# PSPS_AVNC_SRD_fullBoard-2020-09-23.net
KiCad netlist of a schematic drawn in EAGLE
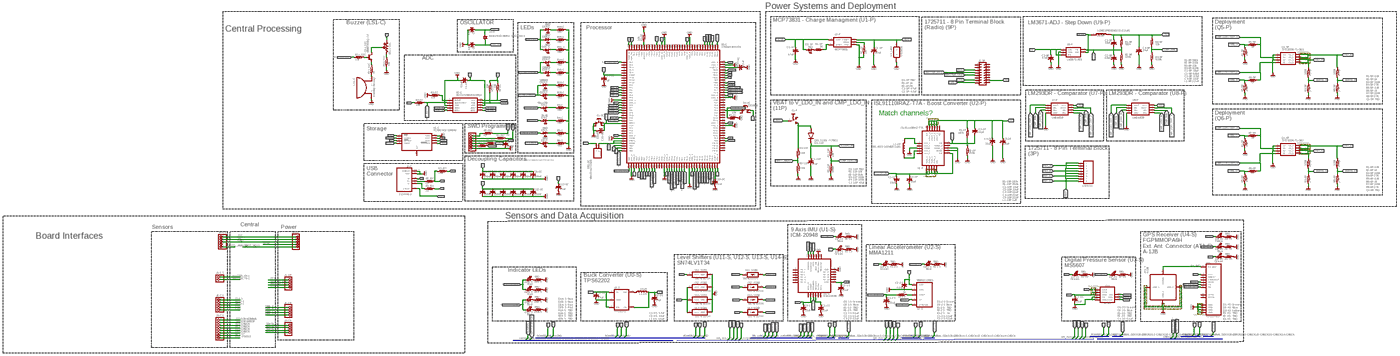
[diagram p0: schematic, sheet 1, overview]
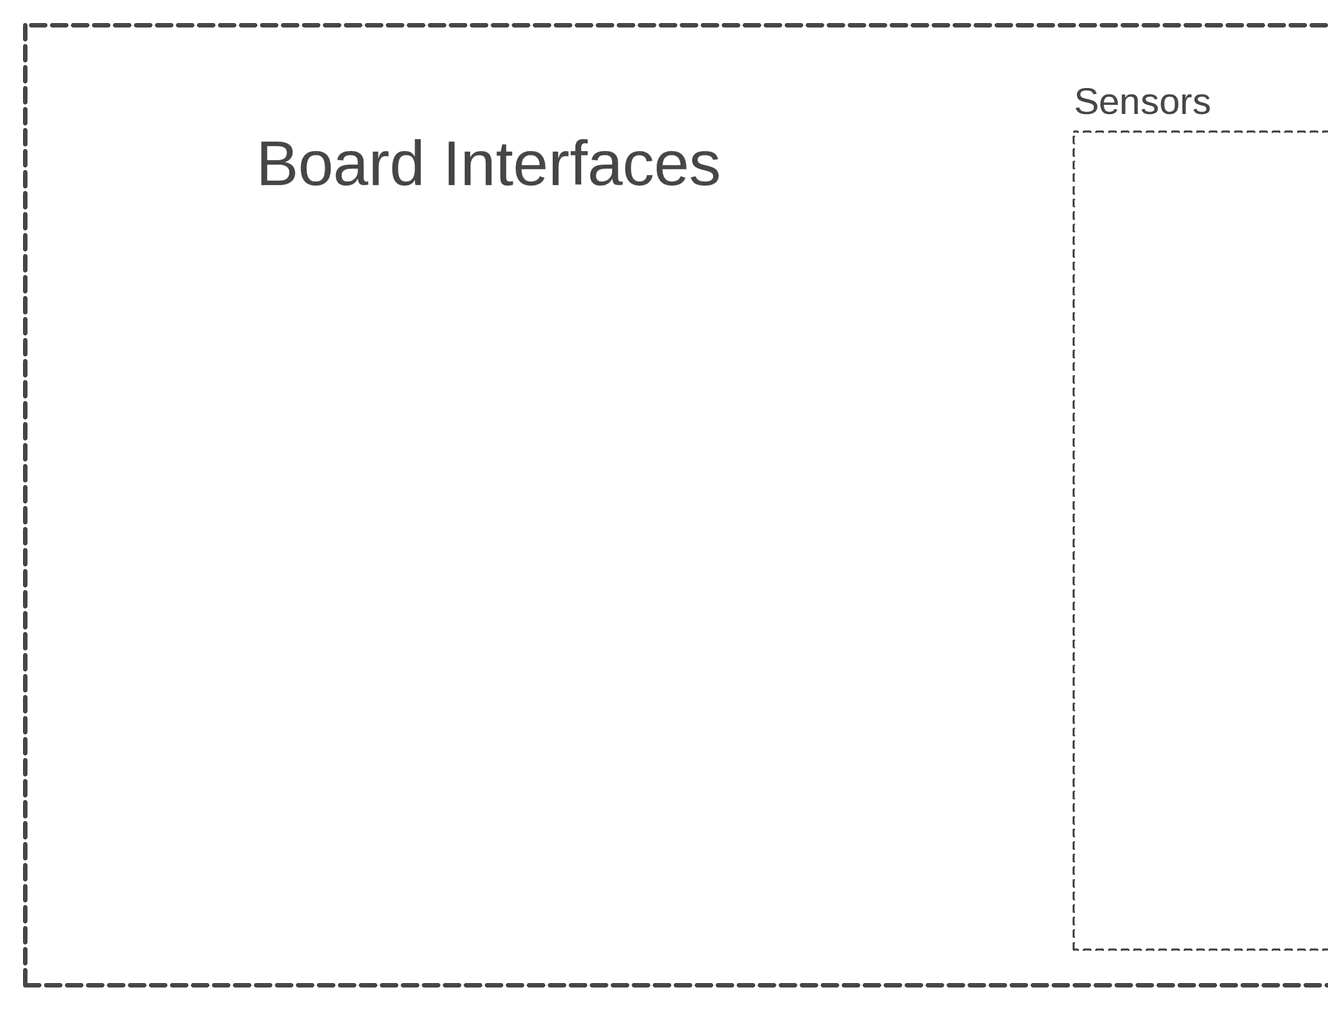
[diagram p1: schematic, sheet 1, part 1 of 4]
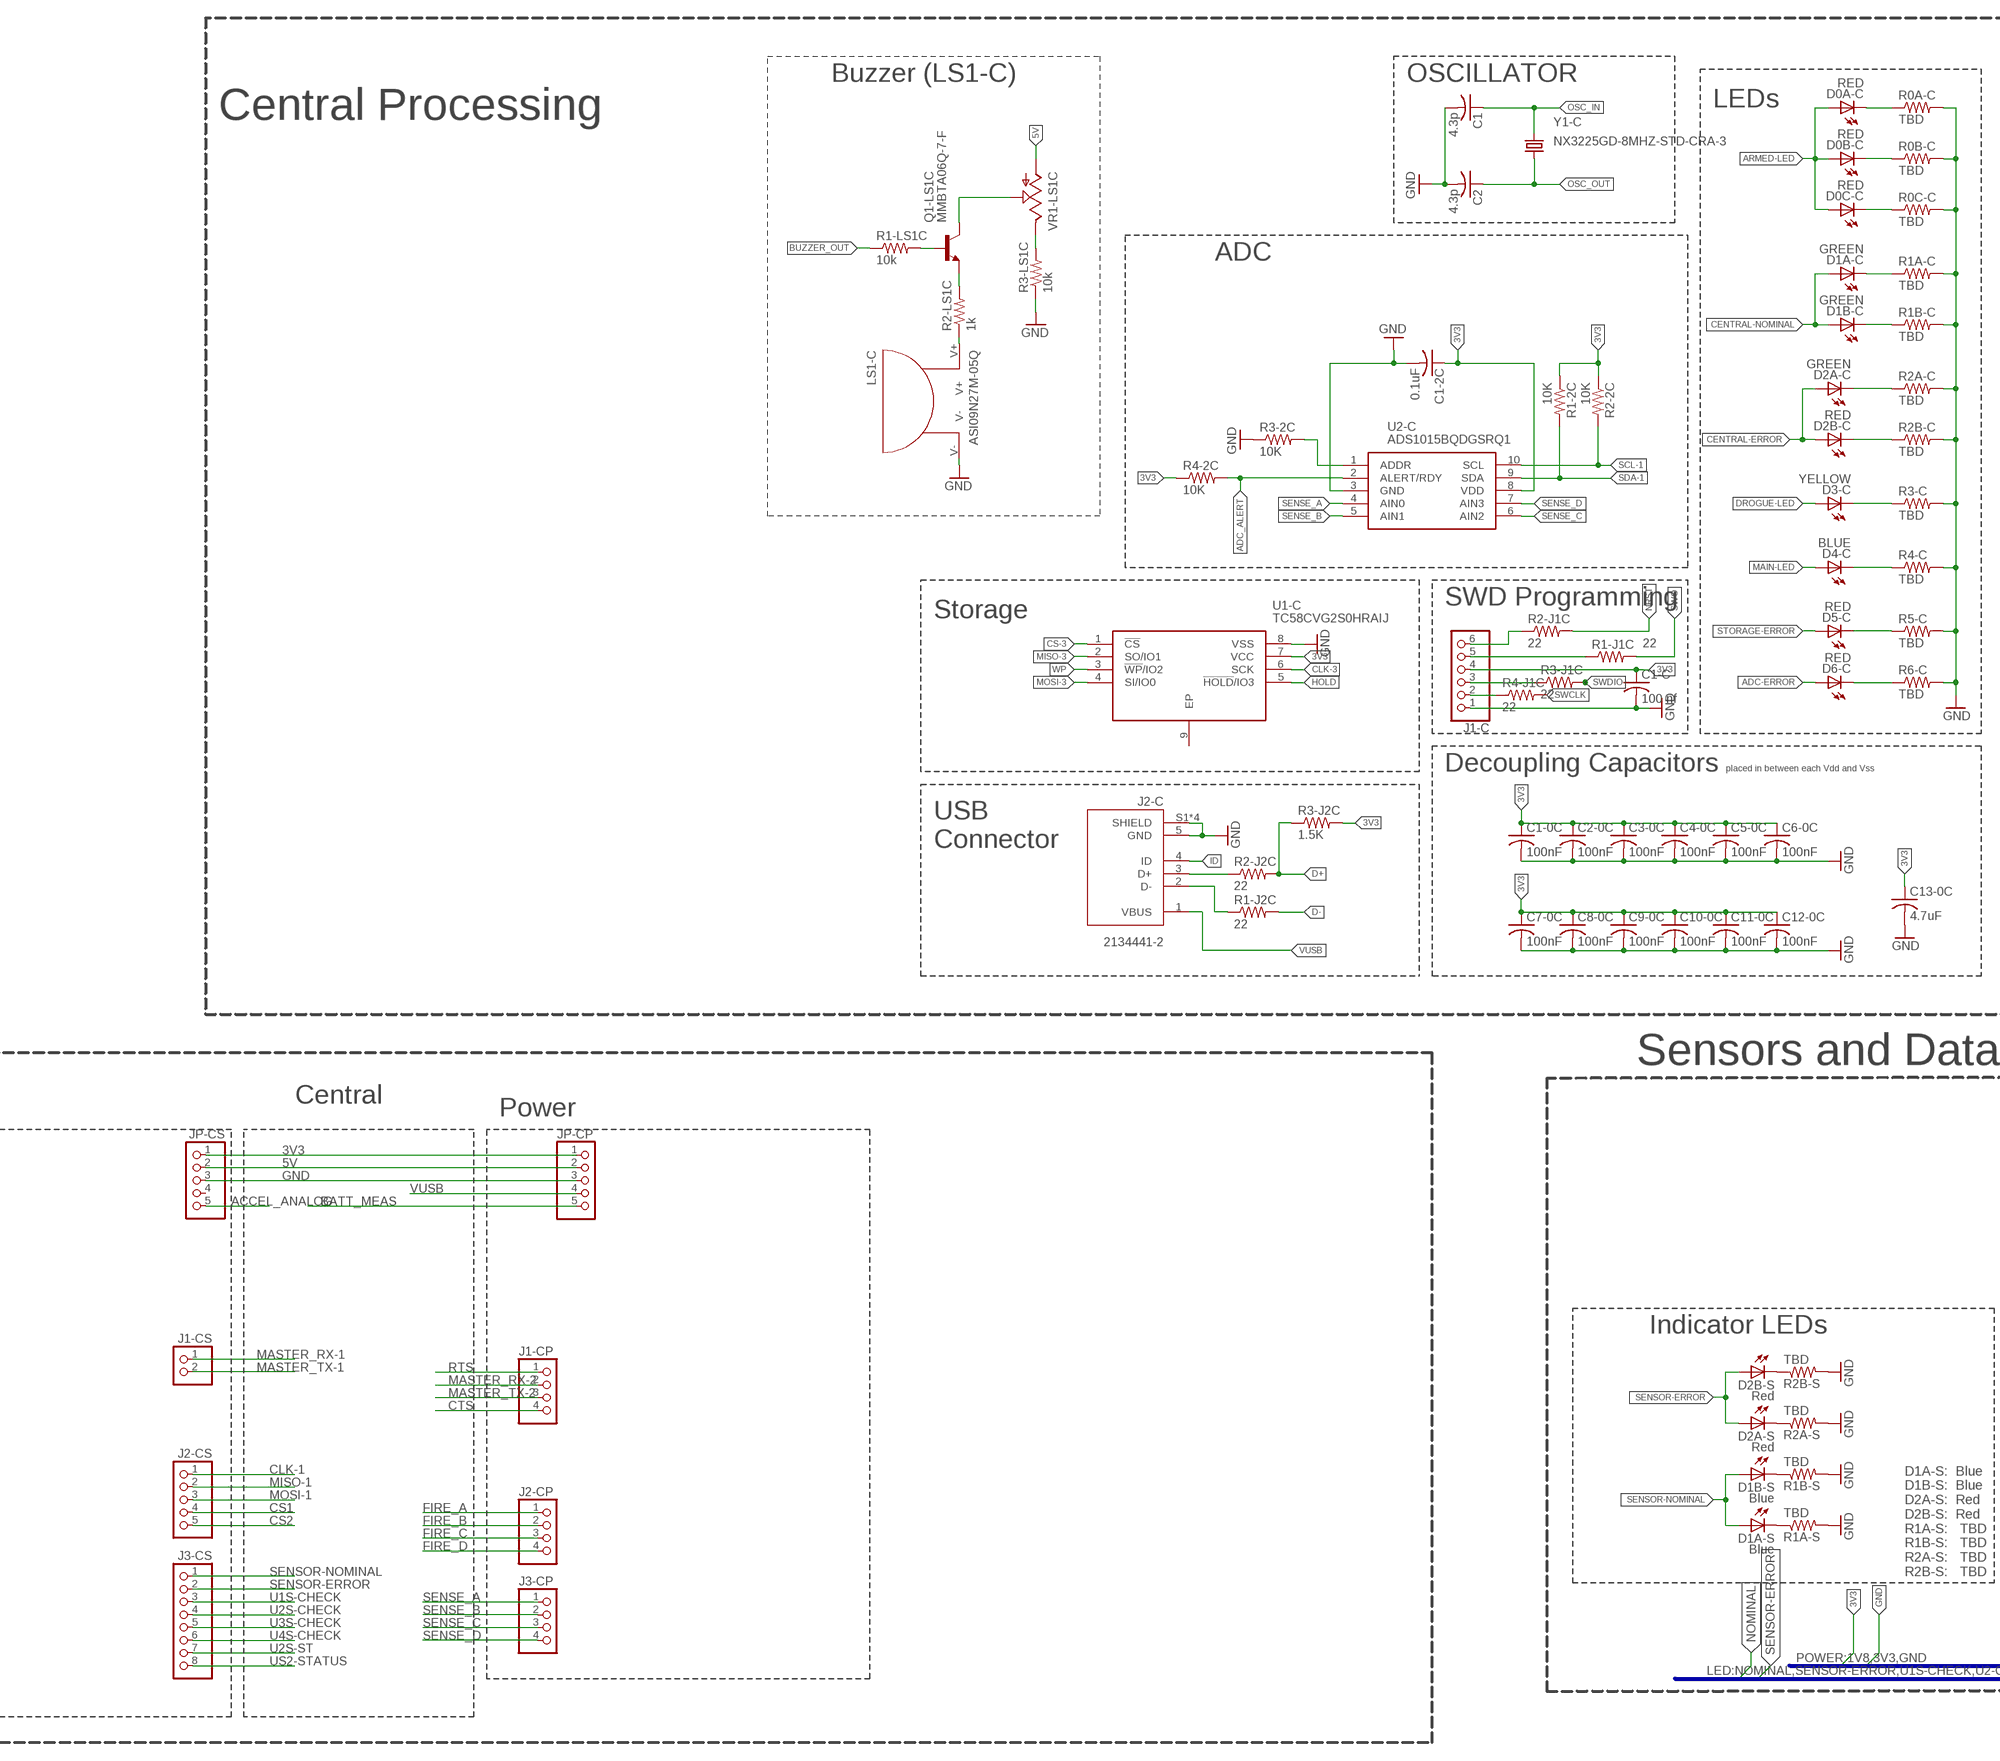
[diagram p2: schematic, sheet 1, part 2 of 4]
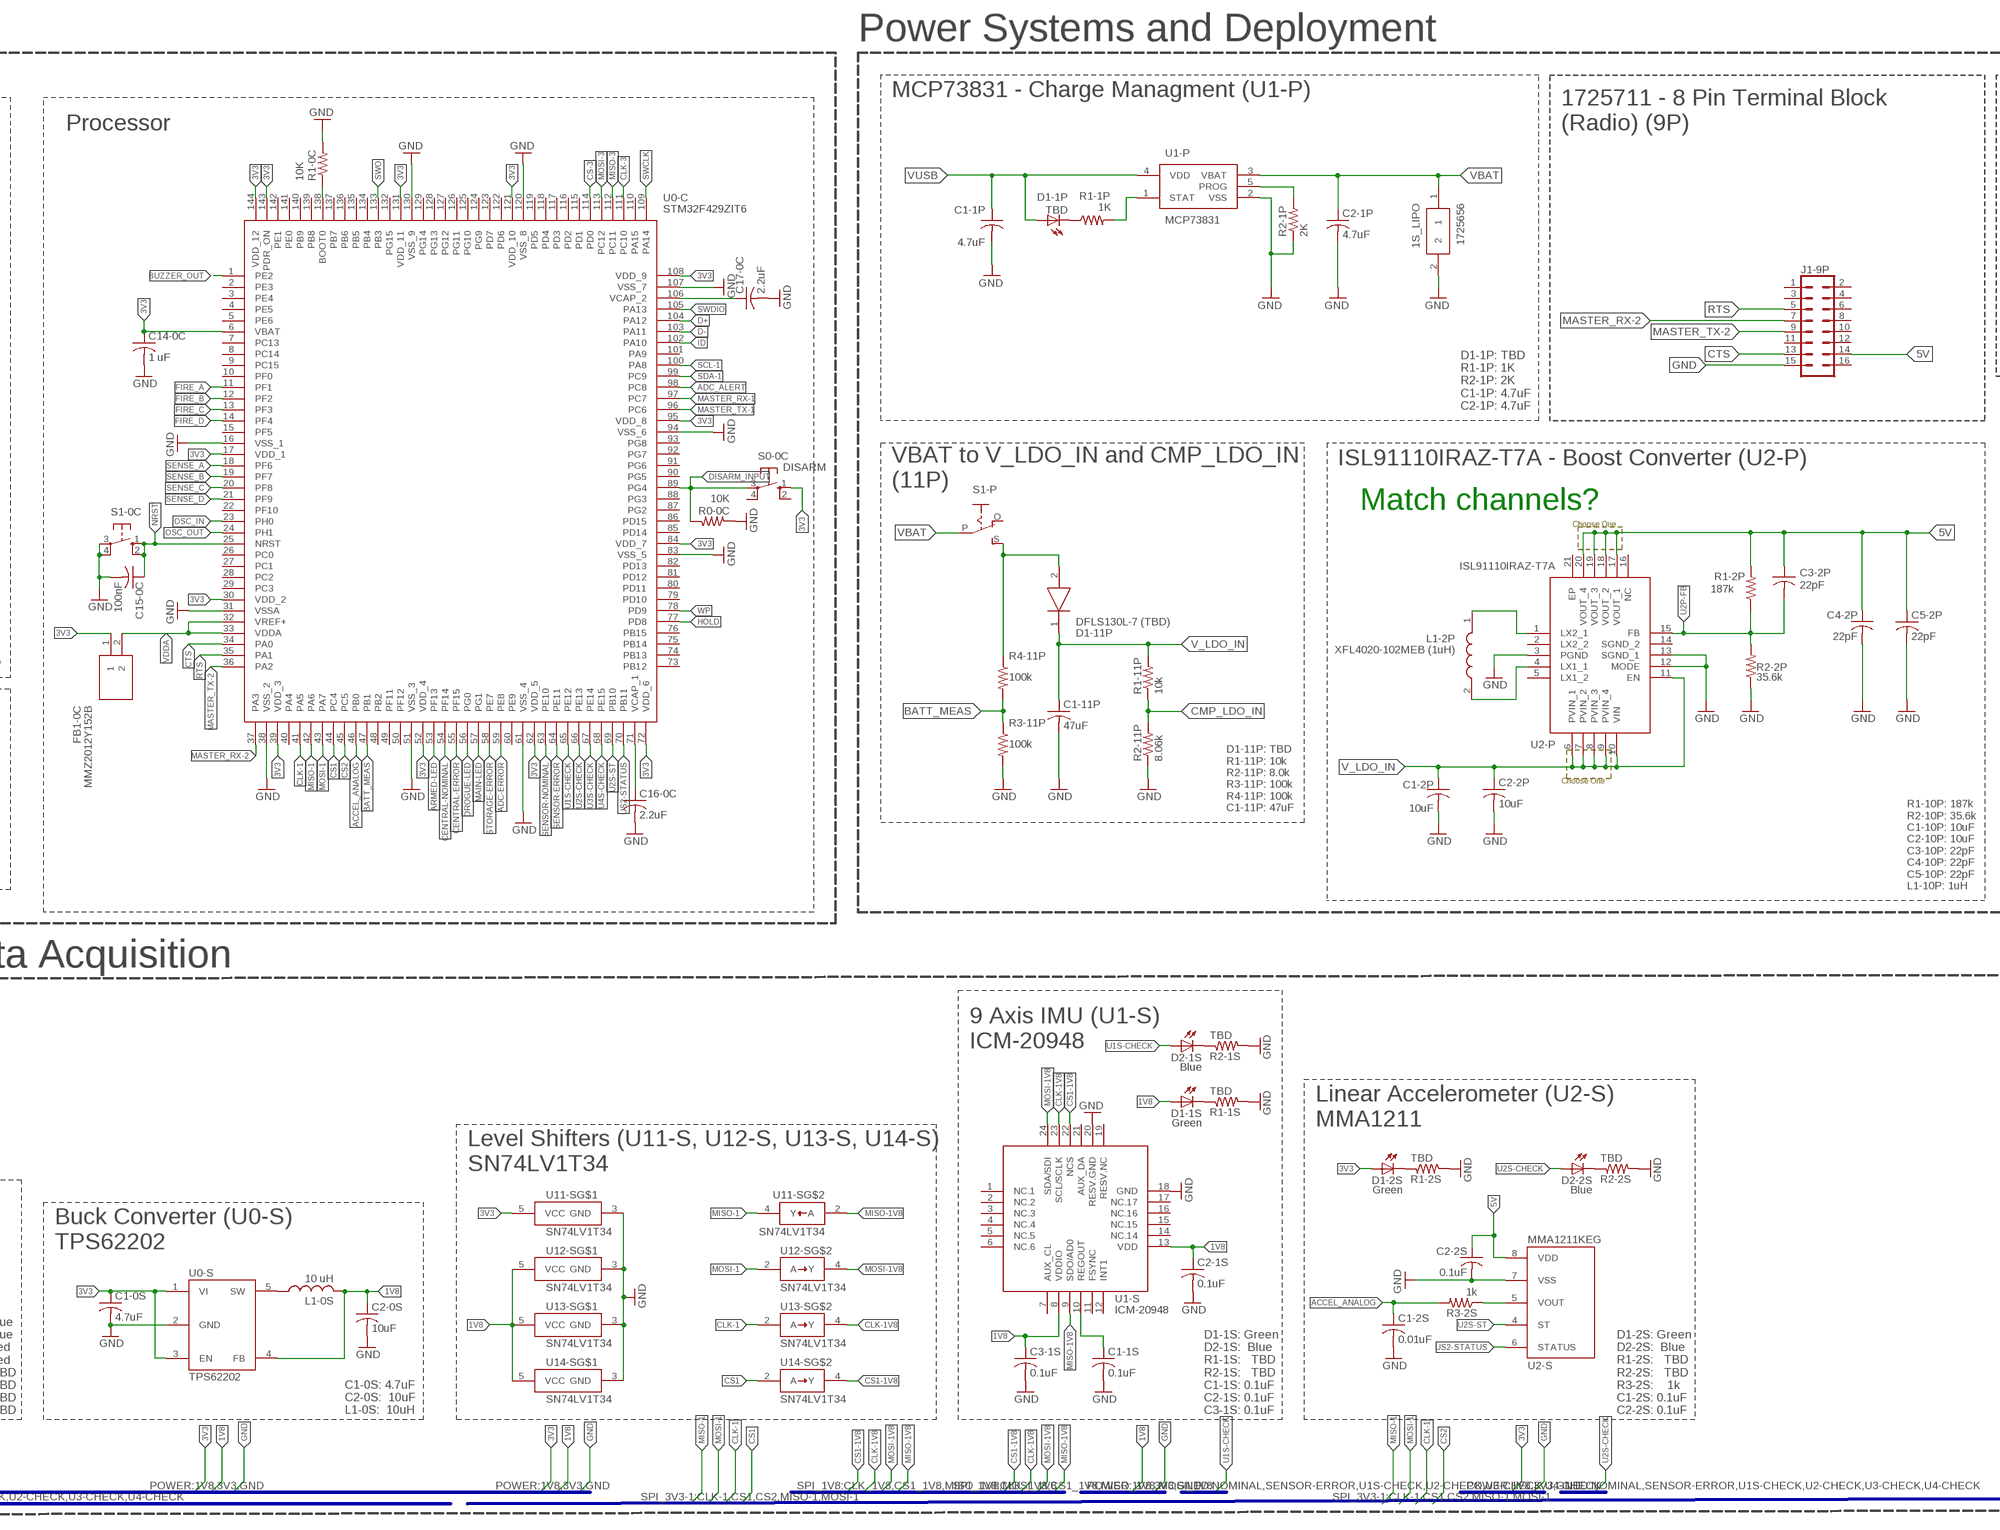
[diagram p3: schematic, sheet 1, part 3 of 4]
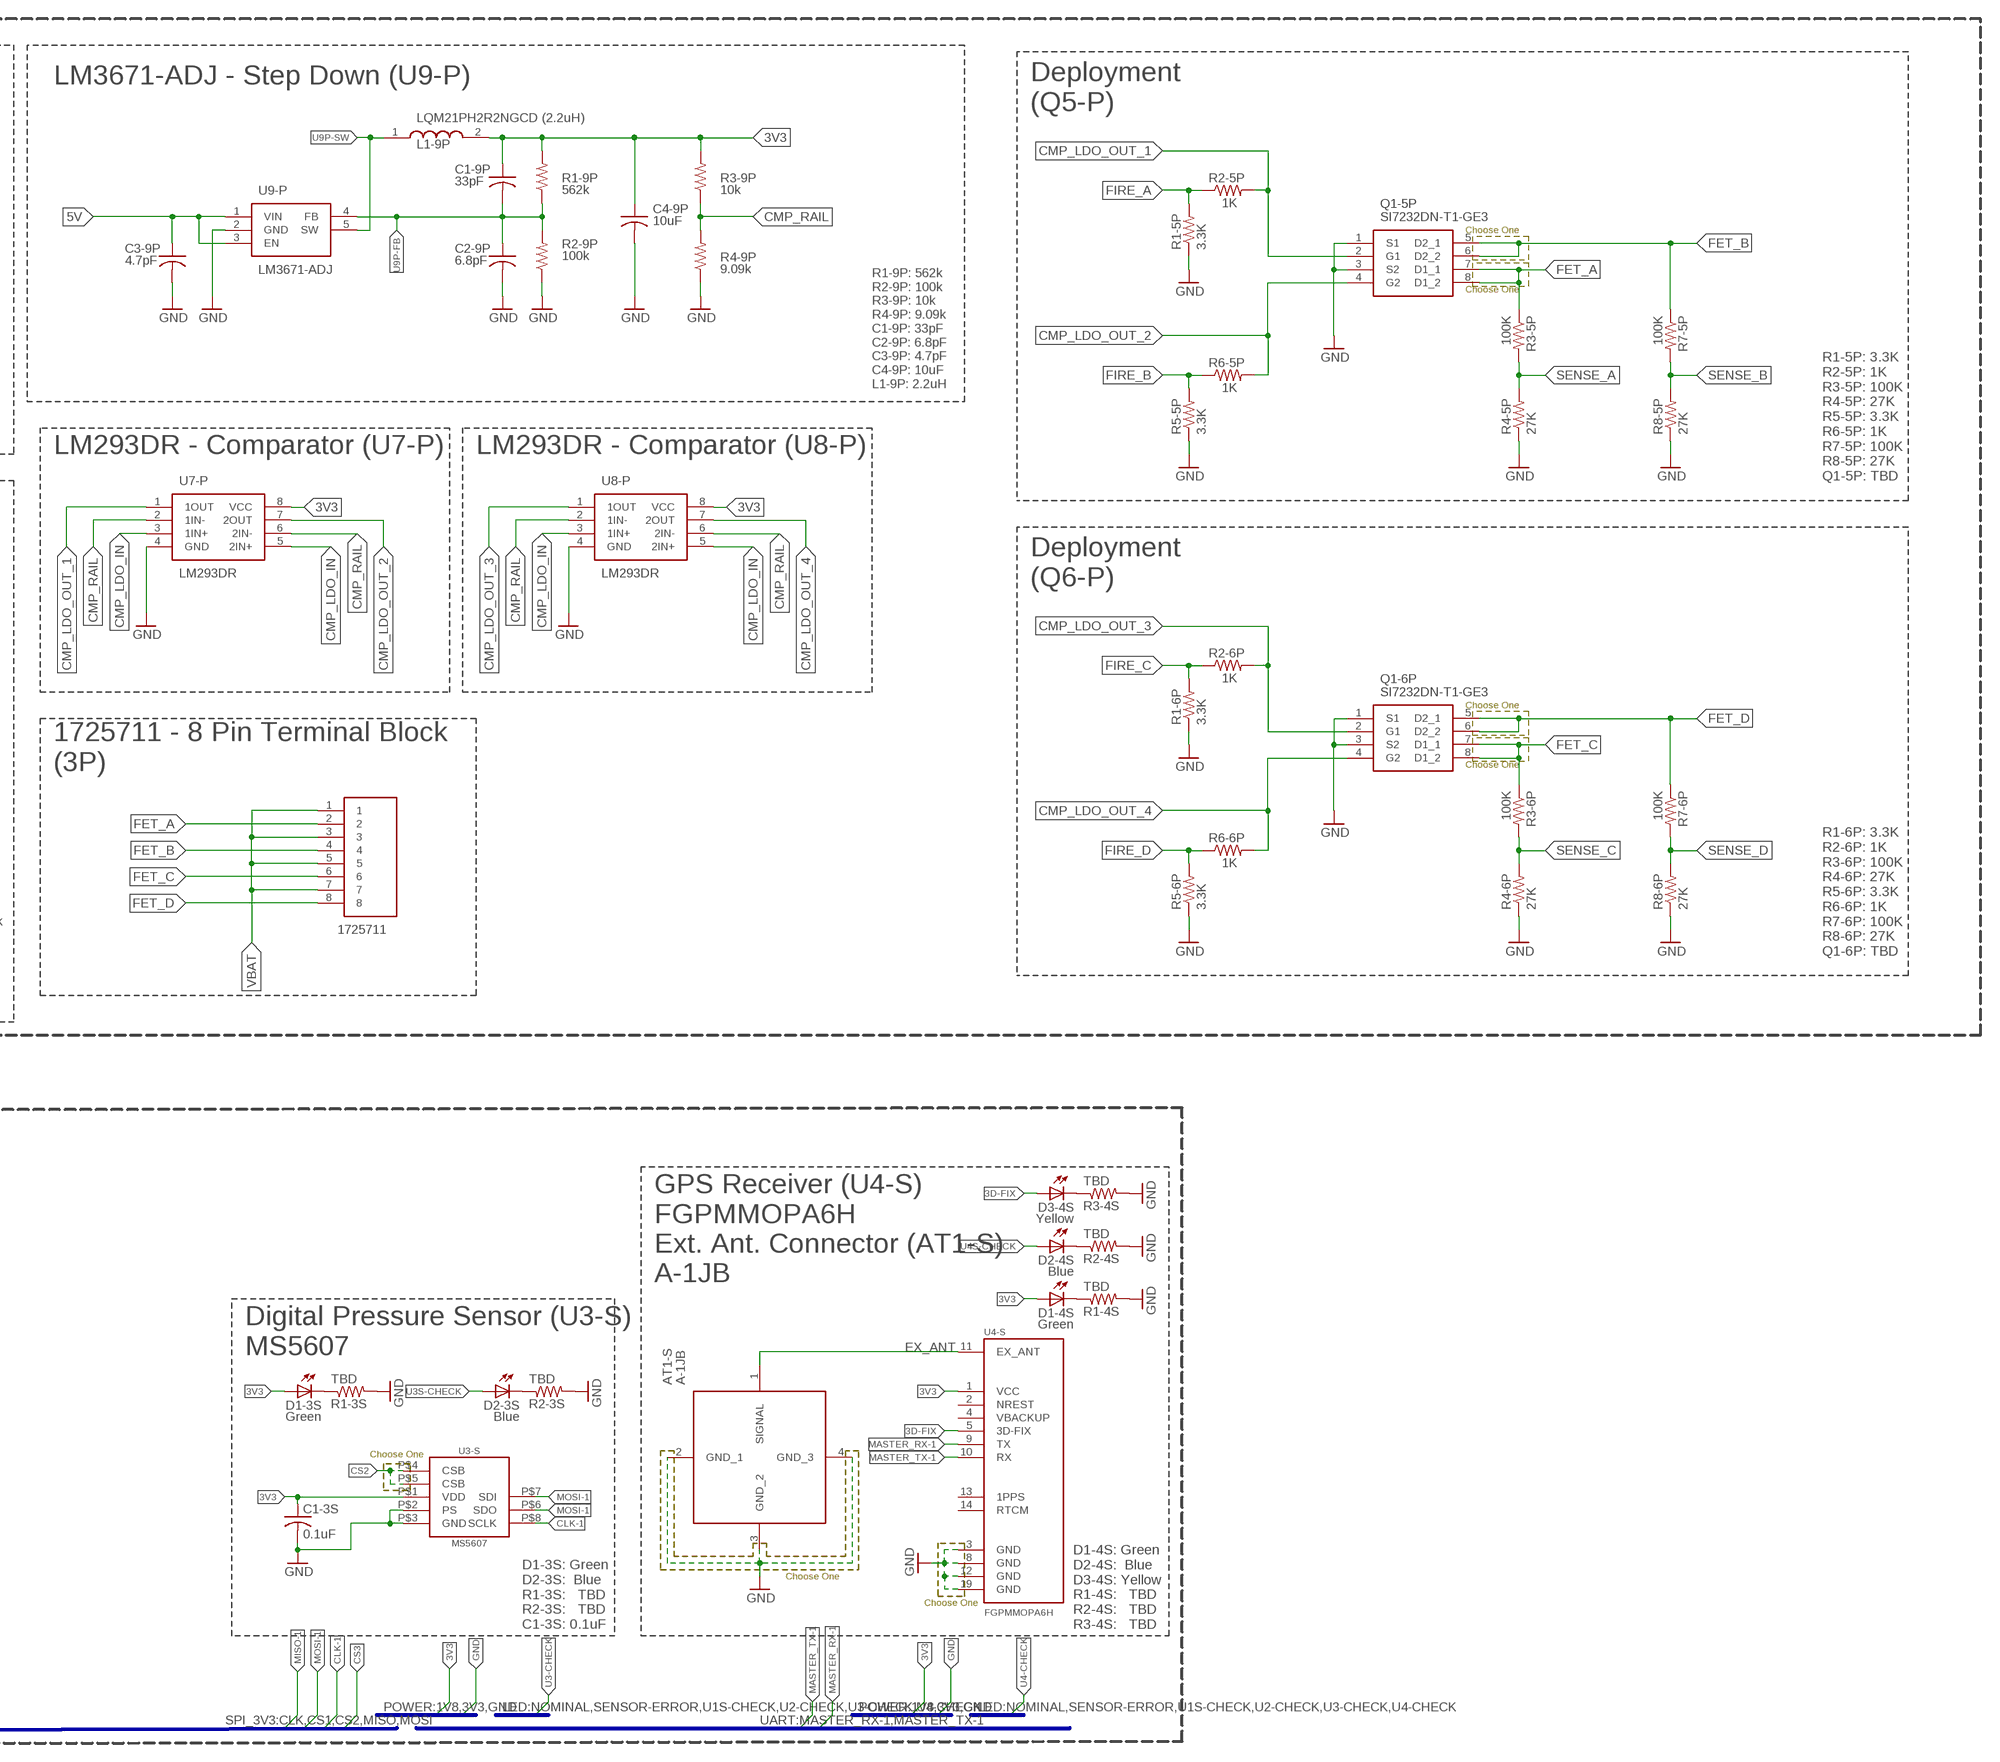
[diagram p4: schematic, sheet 1, part 4 of 4]

(export (version "E")
  (design (tool "Eeschema 10.0.6"))
  (components
    (comp (ref "1S_LIPO")
      (value "1725656")
      (footprint "eagle-import:1725656")
      (fields (field (name "MOUSER_PART_NUMBER") "651-1725656"))
      (libsource (lib "eagle-import") (part "1725656"))
    )
    (comp (ref "AT1-S")
      (value "A-1JB")
      (footprint "eagle-import:A1JB")
      (fields (field (name "MOUSER_PART_NUMBER") "523-A-1JB"))
      (libsource (lib "eagle-import") (part "A-1JB"))
    )
    (comp (ref "C1")
      (value "4.3p")
      (footprint "eagle-import:C0805")
      (libsource (lib "eagle-import") (part "rcl_334_C-USC0805"))
    )
    (comp (ref "C1-0C")
      (value "100nF")
      (footprint "eagle-import:C0805")
      (libsource (lib "eagle-import") (part "rcl_334_C-USC0805"))
    )
    (comp (ref "C1-0S")
      (value "4.7uF")
      (footprint "eagle-import:C0805")
      (libsource (lib "eagle-import") (part "resistor_348_C-USC0805"))
    )
    (comp (ref "C1-1P")
      (value "4.7uF")
      (footprint "eagle-import:C0805")
      (libsource (lib "eagle-import") (part "resistor_348_C-USC0805"))
    )
    (comp (ref "C1-1S")
      (value "0.1uF")
      (footprint "eagle-import:C0805")
      (libsource (lib "eagle-import") (part "resistor_348_C-USC0805"))
    )
    (comp (ref "C1-2C")
      (value "0.1uF")
      (footprint "eagle-import:C0805")
      (libsource (lib "eagle-import") (part "rcl_334_C-USC0805"))
    )
    (comp (ref "C1-2P")
      (value "10uF")
      (footprint "eagle-import:C0805")
      (libsource (lib "eagle-import") (part "resistor_348_C-USC0805"))
    )
    (comp (ref "C1-2S")
      (value "0.01uF")
      (footprint "eagle-import:C0805")
      (libsource (lib "eagle-import") (part "resistor_348_C-USC0805"))
    )
    (comp (ref "C1-3S")
      (value "0.1uF")
      (footprint "eagle-import:C0805")
      (libsource (lib "eagle-import") (part "resistor_348_C-USC0805"))
    )
    (comp (ref "C1-9P")
      (value "33pF")
      (footprint "eagle-import:C0805")
      (libsource (lib "eagle-import") (part "resistor_348_C-USC0805"))
    )
    (comp (ref "C1-11P")
      (value "47uF")
      (footprint "eagle-import:C0805")
      (libsource (lib "eagle-import") (part "resistor_348_C-USC0805"))
    )
    (comp (ref "C1-C")
      (value "100 nf")
      (footprint "eagle-import:C0805")
      (libsource (lib "eagle-import") (part "rcl_334_C-USC0805"))
    )
    (comp (ref "C2")
      (value "4.3p")
      (footprint "eagle-import:C0805")
      (libsource (lib "eagle-import") (part "rcl_334_C-USC0805"))
    )
    (comp (ref "C2-0C")
      (value "100nF")
      (footprint "eagle-import:C0805")
      (libsource (lib "eagle-import") (part "rcl_334_C-USC0805"))
    )
    (comp (ref "C2-0S")
      (value "10uF")
      (footprint "eagle-import:C0805")
      (libsource (lib "eagle-import") (part "resistor_348_C-USC0805"))
    )
    (comp (ref "C2-1P")
      (value "4.7uF")
      (footprint "eagle-import:C0805")
      (libsource (lib "eagle-import") (part "resistor_348_C-USC0805"))
    )
    (comp (ref "C2-1S")
      (value "0.1uF")
      (footprint "eagle-import:C0805")
      (libsource (lib "eagle-import") (part "resistor_348_C-USC0805"))
    )
    (comp (ref "C2-2P")
      (value "10uF")
      (footprint "eagle-import:C0805")
      (libsource (lib "eagle-import") (part "C-USC0805"))
    )
    (comp (ref "C2-2S")
      (value "0.1uF")
      (footprint "eagle-import:C0805")
      (libsource (lib "eagle-import") (part "resistor_348_C-USC0805"))
    )
    (comp (ref "C2-9P")
      (value "6.8pF")
      (footprint "eagle-import:C0805")
      (libsource (lib "eagle-import") (part "resistor_348_C-USC0805"))
    )
    (comp (ref "C3-0C")
      (value "100nF")
      (footprint "eagle-import:C0805")
      (libsource (lib "eagle-import") (part "rcl_334_C-USC0805"))
    )
    (comp (ref "C3-1S")
      (value "0.1uF")
      (footprint "eagle-import:C0805")
      (libsource (lib "eagle-import") (part "resistor_348_C-USC0805"))
    )
    (comp (ref "C3-2P")
      (value "22pF")
      (footprint "eagle-import:C0805")
      (libsource (lib "eagle-import") (part "resistor_348_C-USC0805"))
    )
    (comp (ref "C3-9P")
      (value "4.7pF")
      (footprint "eagle-import:C0805")
      (libsource (lib "eagle-import") (part "resistor_348_C-USC0805"))
    )
    (comp (ref "C4-0C")
      (value "100nF")
      (footprint "eagle-import:C0805")
      (libsource (lib "eagle-import") (part "rcl_334_C-USC0805"))
    )
    (comp (ref "C4-2P")
      (value "22pF")
      (footprint "eagle-import:C0805")
      (fields (field (name "SPICEPREFIX") "C"))
      (libsource (lib "eagle-import") (part "resistor_348_C-USC0805"))
    )
    (comp (ref "C4-9P")
      (value "10uF")
      (footprint "eagle-import:C0805")
      (libsource (lib "eagle-import") (part "resistor_348_C-USC0805"))
    )
    (comp (ref "C5-0C")
      (value "100nF")
      (footprint "eagle-import:C0805")
      (libsource (lib "eagle-import") (part "rcl_334_C-USC0805"))
    )
    (comp (ref "C5-2P")
      (value "22pF")
      (footprint "eagle-import:C0805")
      (libsource (lib "eagle-import") (part "C-USC0805"))
    )
    (comp (ref "C6-0C")
      (value "100nF")
      (footprint "eagle-import:C0805")
      (libsource (lib "eagle-import") (part "rcl_334_C-USC0805"))
    )
    (comp (ref "C7-0C")
      (value "100nF")
      (footprint "eagle-import:C0805")
      (libsource (lib "eagle-import") (part "rcl_334_C-USC0805"))
    )
    (comp (ref "C8-0C")
      (value "100nF")
      (footprint "eagle-import:C0805")
      (libsource (lib "eagle-import") (part "rcl_334_C-USC0805"))
    )
    (comp (ref "C9-0C")
      (value "100nF")
      (footprint "eagle-import:C0805")
      (libsource (lib "eagle-import") (part "rcl_334_C-USC0805"))
    )
    (comp (ref "C10-0C")
      (value "100nF")
      (footprint "eagle-import:C0805")
      (libsource (lib "eagle-import") (part "rcl_334_C-USC0805"))
    )
    (comp (ref "C11-0C")
      (value "100nF")
      (footprint "eagle-import:C0805")
      (libsource (lib "eagle-import") (part "rcl_334_C-USC0805"))
    )
    (comp (ref "C12-0C")
      (value "100nF")
      (footprint "eagle-import:C0805")
      (libsource (lib "eagle-import") (part "rcl_334_C-USC0805"))
    )
    (comp (ref "C13-0C")
      (value "4.7uF")
      (footprint "eagle-import:C0805")
      (libsource (lib "eagle-import") (part "rcl_334_C-USC0805"))
    )
    (comp (ref "C14-0C")
      (value "1 uF")
      (footprint "eagle-import:C0805")
      (libsource (lib "eagle-import") (part "rcl_334_C-USC0805"))
    )
    (comp (ref "C15-0C")
      (value "100nF")
      (footprint "eagle-import:C0805")
      (libsource (lib "eagle-import") (part "rcl_334_C-USC0805"))
    )
    (comp (ref "C16-0C")
      (value "2.2uF")
      (footprint "eagle-import:C0805")
      (libsource (lib "eagle-import") (part "rcl_334_C-USC0805"))
    )
    (comp (ref "C17-0C")
      (value "2.2uF")
      (footprint "eagle-import:C0805")
      (libsource (lib "eagle-import") (part "rcl_334_C-USC0805"))
    )
    (comp (ref "D0A-C")
      (value "RED")
      (footprint "eagle-import:CHIPLED_0805")
      (libsource (lib "eagle-import") (part "adafruit_420_LEDCHIPLED_0805"))
    )
    (comp (ref "D0B-C")
      (value "RED")
      (footprint "eagle-import:CHIPLED_0805")
      (libsource (lib "eagle-import") (part "adafruit_420_LEDCHIPLED_0805"))
    )
    (comp (ref "D0C-C")
      (value "RED")
      (footprint "eagle-import:CHIPLED_0805")
      (libsource (lib "eagle-import") (part "adafruit_420_LEDCHIPLED_0805"))
    )
    (comp (ref "D1-1P")
      (value "TBD")
      (footprint "eagle-import:CHIPLED_0805")
      (libsource (lib "eagle-import") (part "adafruit_420_LEDCHIPLED_0805"))
    )
    (comp (ref "D1-1S")
      (value "Green")
      (footprint "eagle-import:CHIPLED_0805")
      (libsource (lib "eagle-import") (part "LEDCHIPLED_0805"))
    )
    (comp (ref "D1-2S")
      (value "Green")
      (footprint "eagle-import:CHIPLED_0805")
      (libsource (lib "eagle-import") (part "LEDCHIPLED_0805"))
    )
    (comp (ref "D1-3S")
      (value "Green")
      (footprint "eagle-import:CHIPLED_0805")
      (libsource (lib "eagle-import") (part "LEDCHIPLED_0805"))
    )
    (comp (ref "D1-4S")
      (value "Green")
      (footprint "eagle-import:CHIPLED_0805")
      (libsource (lib "eagle-import") (part "LEDCHIPLED_0805"))
    )
    (comp (ref "D1-11P")
      (value "DFLS130L-7 (TBD)")
      (footprint "eagle-import:POWERDI_123")
      (fields
        (field (name "MANUFACTURER_PART_NUMBER") "DFLS130L-7")
        (field (name "MOUSER_PART_NUMBER") "621-DFLS130L")
      )
      (libsource (lib "eagle-import") (part "DFLS130L-7"))
    )
    (comp (ref "D1A-C")
      (value "GREEN")
      (footprint "eagle-import:CHIPLED_0805")
      (libsource (lib "eagle-import") (part "adafruit_420_LEDCHIPLED_0805"))
    )
    (comp (ref "D1A-S")
      (value "Blue")
      (footprint "eagle-import:CHIPLED_0805")
      (libsource (lib "eagle-import") (part "LEDCHIPLED_0805"))
    )
    (comp (ref "D1B-C")
      (value "GREEN")
      (footprint "eagle-import:CHIPLED_0805")
      (libsource (lib "eagle-import") (part "adafruit_420_LEDCHIPLED_0805"))
    )
    (comp (ref "D1B-S")
      (value "Blue")
      (footprint "eagle-import:CHIPLED_0805")
      (libsource (lib "eagle-import") (part "LEDCHIPLED_0805"))
    )
    (comp (ref "D2-1S")
      (value "Blue")
      (footprint "eagle-import:CHIPLED_0805")
      (libsource (lib "eagle-import") (part "LEDCHIPLED_0805"))
    )
    (comp (ref "D2-2S")
      (value "Blue")
      (footprint "eagle-import:CHIPLED_0805")
      (libsource (lib "eagle-import") (part "LEDCHIPLED_0805"))
    )
    (comp (ref "D2-3S")
      (value "Blue")
      (footprint "eagle-import:CHIPLED_0805")
      (libsource (lib "eagle-import") (part "LEDCHIPLED_0805"))
    )
    (comp (ref "D2-4S")
      (value "Blue")
      (footprint "eagle-import:CHIPLED_0805")
      (libsource (lib "eagle-import") (part "LEDCHIPLED_0805"))
    )
    (comp (ref "D2A-C")
      (value "GREEN")
      (footprint "eagle-import:CHIPLED_0805")
      (libsource (lib "eagle-import") (part "adafruit_420_LEDCHIPLED_0805"))
    )
    (comp (ref "D2A-S")
      (value "Red")
      (footprint "eagle-import:CHIPLED_0805")
      (libsource (lib "eagle-import") (part "LEDCHIPLED_0805"))
    )
    (comp (ref "D2B-C")
      (value "RED")
      (footprint "eagle-import:CHIPLED_0805")
      (libsource (lib "eagle-import") (part "adafruit_420_LEDCHIPLED_0805"))
    )
    (comp (ref "D2B-S")
      (value "Red")
      (footprint "eagle-import:CHIPLED_0805")
      (libsource (lib "eagle-import") (part "LEDCHIPLED_0805"))
    )
    (comp (ref "D3-4S")
      (value "Yellow")
      (footprint "eagle-import:CHIPLED_0805")
      (libsource (lib "eagle-import") (part "LEDCHIPLED_0805"))
    )
    (comp (ref "D3-C")
      (value "YELLOW")
      (footprint "eagle-import:CHIPLED_0805")
      (libsource (lib "eagle-import") (part "adafruit_420_LEDCHIPLED_0805"))
    )
    (comp (ref "D4-C")
      (value "BLUE")
      (footprint "eagle-import:CHIPLED_0805")
      (libsource (lib "eagle-import") (part "adafruit_420_LEDCHIPLED_0805"))
    )
    (comp (ref "D5-C")
      (value "RED")
      (footprint "eagle-import:CHIPLED_0805")
      (libsource (lib "eagle-import") (part "adafruit_420_LEDCHIPLED_0805"))
    )
    (comp (ref "D6-C")
      (value "RED")
      (footprint "eagle-import:CHIPLED_0805")
      (libsource (lib "eagle-import") (part "adafruit_420_LEDCHIPLED_0805"))
    )
    (comp (ref "FB1-0C")
      (value "MMZ2012Y152B")
      (footprint "eagle-import:BEADC2012X105N")
      (fields (field (name "MOUSER_PART_NUMBER") "810-MMZ2012Y152B"))
      (libsource (lib "eagle-import") (part "MMZ2012Y152B"))
    )
    (comp (ref "J1-9P")
      (value "CONN_08X2")
      (footprint "eagle-import:2X8")
      (libsource (lib "eagle-import") (part "CONN_08X2"))
    )
    (comp (ref "J1-C")
      (value "PINHD-1X6")
      (footprint "eagle-import:1X06")
      (libsource (lib "eagle-import") (part "PINHD-1X6"))
    )
    (comp (ref "J1-CP")
      (value "PINHD-1X4")
      (footprint "eagle-import:1X04")
      (libsource (lib "eagle-import") (part "PINHD-1X4"))
    )
    (comp (ref "J1-CS")
      (value "PINHD-1X2")
      (footprint "eagle-import:1X02")
      (libsource (lib "eagle-import") (part "PINHD-1X2"))
    )
    (comp (ref "J2-C")
      (value "2134441-2")
      (footprint "eagle-import:TE_2134441-2")
      (fields (field (name "DIGI-KEY_PART_NUMBER") "A118104CT-ND") (field (name "MF") "TE Connectivity"))
      (libsource (lib "eagle-import") (part "2134441-2"))
    )
    (comp (ref "J2-CP")
      (value "PINHD-1X4")
      (footprint "eagle-import:1X04")
      (libsource (lib "eagle-import") (part "PINHD-1X4"))
    )
    (comp (ref "J2-CS")
      (value "PINHD-1X5")
      (footprint "eagle-import:1X05")
      (libsource (lib "eagle-import") (part "PINHD-1X5"))
    )
    (comp (ref "J2-P")
      (value "1725711")
      (footprint "eagle-import:1725711")
      (fields (field (name "MOUSER_PART_NUMBER") "651-1725711"))
      (libsource (lib "eagle-import") (part "1725711"))
    )
    (comp (ref "J3-CP")
      (value "PINHD-1X4")
      (footprint "eagle-import:1X04")
      (libsource (lib "eagle-import") (part "PINHD-1X4"))
    )
    (comp (ref "J3-CS")
      (value "PINHD-1X8")
      (footprint "eagle-import:1X08")
      (libsource (lib "eagle-import") (part "PINHD-1X8"))
    )
    (comp (ref "JP-CP")
      (value "PINHD-1X5")
      (footprint "eagle-import:1X05")
      (libsource (lib "eagle-import") (part "PINHD-1X5"))
    )
    (comp (ref "JP-CS")
      (value "PINHD-1X5")
      (footprint "eagle-import:1X05")
      (libsource (lib "eagle-import") (part "PINHD-1X5"))
    )
    (comp (ref "L1-0S")
      (value "10 uH")
      (footprint "eagle-import:PF0560NL")
      (libsource (lib "eagle-import") (part "PF0560.103NLT"))
    )
    (comp (ref "L1-2P")
      (value "XFL4020-102MEB (1uH)")
      (footprint "eagle-import:XFL4020")
      (fields
        (field (name "MANUFACTURER_PART_NUMBER") "XFL4020-102MEB")
        (field (name "MOUSER_PART_NUMBER") "994-XFL4020-102MEB")
      )
      (libsource (lib "eagle-import") (part "XFL4020-102MEB"))
    )
    (comp (ref "L1-9P")
      (value "LQM21PH2R2NGCD (2.2uH)")
      (footprint "eagle-import:INDC2012X100N")
      (fields
        (field (name "MANUFACTURER_PART_NUMBER") "LQM21PH2R2NGCD")
        (field (name "MOUSER_PART_NUMBER") "81-LQM21PH2R2NGCD")
      )
      (libsource (lib "eagle-import") (part "LQM21PH2R2NGCD"))
    )
    (comp (ref "LS1-C")
      (value "ASI09N27M-05Q")
      (footprint "eagle-import:ASI09N27M-05Q")
      (libsource (lib "eagle-import") (part "ASI09N27M-05Q"))
    )
    (comp (ref "Q1-5P")
      (value "SI7232DN-T1-GE3")
      (footprint "eagle-import:POWERPAK-1212-8")
      (fields (field (name "MOUSER_PART_NUMBER") "781-SI7232DN-GE3"))
      (libsource (lib "eagle-import") (part "SI7232DN-T1-GE3"))
    )
    (comp (ref "Q1-6P")
      (value "SI7232DN-T1-GE3")
      (footprint "eagle-import:POWERPAK-1212-8")
      (fields (field (name "MOUSER_PART_NUMBER") "781-SI7232DN-GE3"))
      (libsource (lib "eagle-import") (part "SI7232DN-T1-GE3"))
    )
    (comp (ref "Q1-LS1C")
      (value "MMBTA06Q-7-F")
      (footprint "eagle-import:SOT23")
      (libsource (lib "eagle-import") (part "NPN_TRANSISTOR"))
    )
    (comp (ref "R0-0C")
      (value "10K")
      (footprint "eagle-import:R0805")
      (libsource (lib "eagle-import") (part "rcl_334_R-US_R0805"))
    )
    (comp (ref "R0A-C")
      (value "TBD")
      (footprint "eagle-import:M0805")
      (libsource (lib "eagle-import") (part "rcl_334_R-US_M0805"))
    )
    (comp (ref "R0B-C")
      (value "TBD")
      (footprint "eagle-import:M0805")
      (libsource (lib "eagle-import") (part "rcl_334_R-US_M0805"))
    )
    (comp (ref "R0C-C")
      (value "TBD")
      (footprint "eagle-import:M0805")
      (libsource (lib "eagle-import") (part "rcl_334_R-US_M0805"))
    )
    (comp (ref "R1-0C")
      (value "10K")
      (footprint "eagle-import:R0805")
      (libsource (lib "eagle-import") (part "rcl_334_R-US_R0805"))
    )
    (comp (ref "R1-1P")
      (value "1K")
      (footprint "eagle-import:R0805")
      (libsource (lib "eagle-import") (part "resistor_348_R-US_R0805"))
    )
    (comp (ref "R1-1S")
      (value "TBD")
      (footprint "eagle-import:R0805")
      (libsource (lib "eagle-import") (part "resistor_348_R-US_R0805"))
    )
    (comp (ref "R1-2C")
      (value "10K")
      (footprint "eagle-import:R0805")
      (libsource (lib "eagle-import") (part "rcl_334_R-US_R0805"))
    )
    (comp (ref "R1-2P")
      (value "187k")
      (footprint "eagle-import:R0805")
      (libsource (lib "eagle-import") (part "resistor_348_R-US_R0805"))
    )
    (comp (ref "R1-2S")
      (value "TBD")
      (footprint "eagle-import:R0805")
      (libsource (lib "eagle-import") (part "resistor_348_R-US_R0805"))
    )
    (comp (ref "R1-3S")
      (value "TBD")
      (footprint "eagle-import:R0805")
      (libsource (lib "eagle-import") (part "resistor_348_R-US_R0805"))
    )
    (comp (ref "R1-4S")
      (value "TBD")
      (footprint "eagle-import:R0805")
      (libsource (lib "eagle-import") (part "resistor_348_R-US_R0805"))
    )
    (comp (ref "R1-5P")
      (value "3.3K")
      (footprint "eagle-import:M0805")
      (libsource (lib "eagle-import") (part "rcl_334_R-US_M0805"))
    )
    (comp (ref "R1-6P")
      (value "3.3K")
      (footprint "eagle-import:M0805")
      (libsource (lib "eagle-import") (part "rcl_334_R-US_M0805"))
    )
    (comp (ref "R1-9P")
      (value "562k")
      (footprint "eagle-import:R0805")
      (libsource (lib "eagle-import") (part "resistor_348_R-US_R0805"))
    )
    (comp (ref "R1-11P")
      (value "10k")
      (footprint "eagle-import:R0805")
      (libsource (lib "eagle-import") (part "resistor_348_R-US_R0805"))
    )
    (comp (ref "R1-J1C")
      (value "22")
      (footprint "eagle-import:M0805")
      (libsource (lib "eagle-import") (part "rcl_334_R-US_M0805"))
    )
    (comp (ref "R1-J2C")
      (value "22")
      (footprint "eagle-import:M0805")
      (libsource (lib "eagle-import") (part "rcl_334_R-US_M0805"))
    )
    (comp (ref "R1-LS1C")
      (value "10k")
      (footprint "eagle-import:R0805")
      (libsource (lib "eagle-import") (part "resistor_348_R-US_R0805"))
    )
    (comp (ref "R1A-C")
      (value "TBD")
      (footprint "eagle-import:M0805")
      (libsource (lib "eagle-import") (part "rcl_334_R-US_M0805"))
    )
    (comp (ref "R1A-S")
      (value "TBD")
      (footprint "eagle-import:R0805")
      (libsource (lib "eagle-import") (part "resistor_348_R-US_R0805"))
    )
    (comp (ref "R1B-C")
      (value "TBD")
      (footprint "eagle-import:M0805")
      (libsource (lib "eagle-import") (part "rcl_334_R-US_M0805"))
    )
    (comp (ref "R1B-S")
      (value "TBD")
      (footprint "eagle-import:R0805")
      (libsource (lib "eagle-import") (part "resistor_348_R-US_R0805"))
    )
    (comp (ref "R2-1P")
      (value "2K")
      (footprint "eagle-import:R0805")
      (libsource (lib "eagle-import") (part "resistor_348_R-US_R0805"))
    )
    (comp (ref "R2-1S")
      (value "TBD")
      (footprint "eagle-import:R0805")
      (libsource (lib "eagle-import") (part "resistor_348_R-US_R0805"))
    )
    (comp (ref "R2-2C")
      (value "10K")
      (footprint "eagle-import:R0805")
      (libsource (lib "eagle-import") (part "rcl_334_R-US_R0805"))
    )
    (comp (ref "R2-2P")
      (value "35.6k")
      (footprint "eagle-import:R0805")
      (libsource (lib "eagle-import") (part "resistor_348_R-US_R0805"))
    )
    (comp (ref "R2-2S")
      (value "TBD")
      (footprint "eagle-import:R0805")
      (libsource (lib "eagle-import") (part "resistor_348_R-US_R0805"))
    )
    (comp (ref "R2-3S")
      (value "TBD")
      (footprint "eagle-import:R0805")
      (libsource (lib "eagle-import") (part "resistor_348_R-US_R0805"))
    )
    (comp (ref "R2-4S")
      (value "TBD")
      (footprint "eagle-import:R0805")
      (libsource (lib "eagle-import") (part "resistor_348_R-US_R0805"))
    )
    (comp (ref "R2-5P")
      (value "1K")
      (footprint "eagle-import:M0805")
      (libsource (lib "eagle-import") (part "rcl_334_R-US_M0805"))
    )
    (comp (ref "R2-6P")
      (value "1K")
      (footprint "eagle-import:M0805")
      (libsource (lib "eagle-import") (part "rcl_334_R-US_M0805"))
    )
    (comp (ref "R2-9P")
      (value "100k")
      (footprint "eagle-import:R0805")
      (libsource (lib "eagle-import") (part "resistor_348_R-US_R0805"))
    )
    (comp (ref "R2-11P")
      (value "8.06k")
      (footprint "eagle-import:R0805")
      (libsource (lib "eagle-import") (part "resistor_348_R-US_R0805"))
    )
    (comp (ref "R2-J1C")
      (value "22")
      (footprint "eagle-import:M0805")
      (libsource (lib "eagle-import") (part "rcl_334_R-US_M0805"))
    )
    (comp (ref "R2-J2C")
      (value "22")
      (footprint "eagle-import:M0805")
      (libsource (lib "eagle-import") (part "rcl_334_R-US_M0805"))
    )
    (comp (ref "R2-LS1C")
      (value "1k")
      (footprint "eagle-import:R0805")
      (libsource (lib "eagle-import") (part "resistor_348_R-US_R0805"))
    )
    (comp (ref "R2A-C")
      (value "TBD")
      (footprint "eagle-import:M0805")
      (libsource (lib "eagle-import") (part "rcl_334_R-US_M0805"))
    )
    (comp (ref "R2A-S")
      (value "TBD")
      (footprint "eagle-import:R0805")
      (libsource (lib "eagle-import") (part "resistor_348_R-US_R0805"))
    )
    (comp (ref "R2B-C")
      (value "TBD")
      (footprint "eagle-import:M0805")
      (libsource (lib "eagle-import") (part "rcl_334_R-US_M0805"))
    )
    (comp (ref "R2B-S")
      (value "TBD")
      (footprint "eagle-import:R0805")
      (libsource (lib "eagle-import") (part "resistor_348_R-US_R0805"))
    )
    (comp (ref "R3-2C")
      (value "10K")
      (footprint "eagle-import:R0805")
      (libsource (lib "eagle-import") (part "rcl_334_R-US_R0805"))
    )
    (comp (ref "R3-2S")
      (value "1k")
      (footprint "eagle-import:R0805")
      (libsource (lib "eagle-import") (part "resistor_348_R-US_R0805"))
    )
    (comp (ref "R3-4S")
      (value "TBD")
      (footprint "eagle-import:R0805")
      (libsource (lib "eagle-import") (part "resistor_348_R-US_R0805"))
    )
    (comp (ref "R3-5P")
      (value "100K")
      (footprint "eagle-import:M0805")
      (libsource (lib "eagle-import") (part "rcl_334_R-US_M0805"))
    )
    (comp (ref "R3-6P")
      (value "100K")
      (footprint "eagle-import:M0805")
      (libsource (lib "eagle-import") (part "rcl_334_R-US_M0805"))
    )
    (comp (ref "R3-9P")
      (value "10k")
      (footprint "eagle-import:R0805")
      (libsource (lib "eagle-import") (part "resistor_348_R-US_R0805"))
    )
    (comp (ref "R3-11P")
      (value "100k")
      (footprint "eagle-import:R0805")
      (libsource (lib "eagle-import") (part "R-US_R0805"))
    )
    (comp (ref "R3-C")
      (value "TBD")
      (footprint "eagle-import:M0805")
      (libsource (lib "eagle-import") (part "rcl_334_R-US_M0805"))
    )
    (comp (ref "R3-J1C")
      (value "22")
      (footprint "eagle-import:M0805")
      (libsource (lib "eagle-import") (part "rcl_334_R-US_M0805"))
    )
    (comp (ref "R3-J2C")
      (value "1.5K")
      (footprint "eagle-import:M0805")
      (libsource (lib "eagle-import") (part "rcl_334_R-US_M0805"))
    )
    (comp (ref "R3-LS1C")
      (value "10k")
      (footprint "eagle-import:R0805")
      (libsource (lib "eagle-import") (part "resistor_348_R-US_R0805"))
    )
    (comp (ref "R4-2C")
      (value "10K")
      (footprint "eagle-import:R0805")
      (libsource (lib "eagle-import") (part "rcl_334_R-US_R0805"))
    )
    (comp (ref "R4-5P")
      (value "27K")
      (footprint "eagle-import:M0805")
      (libsource (lib "eagle-import") (part "rcl_334_R-US_M0805"))
    )
    (comp (ref "R4-6P")
      (value "27K")
      (footprint "eagle-import:M0805")
      (libsource (lib "eagle-import") (part "rcl_334_R-US_M0805"))
    )
    (comp (ref "R4-9P")
      (value "9.09k")
      (footprint "eagle-import:R0805")
      (libsource (lib "eagle-import") (part "resistor_348_R-US_R0805"))
    )
    (comp (ref "R4-11P")
      (value "100k")
      (footprint "eagle-import:R0805")
      (libsource (lib "eagle-import") (part "R-US_R0805"))
    )
    (comp (ref "R4-C")
      (value "TBD")
      (footprint "eagle-import:M0805")
      (libsource (lib "eagle-import") (part "rcl_334_R-US_M0805"))
    )
    (comp (ref "R4-J1C")
      (value "22")
      (footprint "eagle-import:M0805")
      (libsource (lib "eagle-import") (part "rcl_334_R-US_M0805"))
    )
    (comp (ref "R5-5P")
      (value "3.3K")
      (footprint "eagle-import:M0805")
      (libsource (lib "eagle-import") (part "rcl_334_R-US_M0805"))
    )
    (comp (ref "R5-6P")
      (value "3.3K")
      (footprint "eagle-import:M0805")
      (libsource (lib "eagle-import") (part "rcl_334_R-US_M0805"))
    )
    (comp (ref "R5-C")
      (value "TBD")
      (footprint "eagle-import:M0805")
      (libsource (lib "eagle-import") (part "rcl_334_R-US_M0805"))
    )
    (comp (ref "R6-5P")
      (value "1K")
      (footprint "eagle-import:M0805")
      (libsource (lib "eagle-import") (part "rcl_334_R-US_M0805"))
    )
    (comp (ref "R6-6P")
      (value "1K")
      (footprint "eagle-import:M0805")
      (libsource (lib "eagle-import") (part "rcl_334_R-US_M0805"))
    )
    (comp (ref "R6-C")
      (value "TBD")
      (footprint "eagle-import:M0805")
      (libsource (lib "eagle-import") (part "rcl_334_R-US_M0805"))
    )
    (comp (ref "R7-5P")
      (value "100K")
      (footprint "eagle-import:M0805")
      (libsource (lib "eagle-import") (part "rcl_334_R-US_M0805"))
    )
    (comp (ref "R7-6P")
      (value "100K")
      (footprint "eagle-import:M0805")
      (libsource (lib "eagle-import") (part "rcl_334_R-US_M0805"))
    )
    (comp (ref "R8-5P")
      (value "27K")
      (footprint "eagle-import:M0805")
      (libsource (lib "eagle-import") (part "rcl_334_R-US_M0805"))
    )
    (comp (ref "R8-6P")
      (value "27K")
      (footprint "eagle-import:M0805")
      (libsource (lib "eagle-import") (part "rcl_334_R-US_M0805"))
    )
    (comp (ref "S0-0C")
      (value "DISARM")
      (footprint "eagle-import:B3F-10XX")
      (fields (field (name "MPN") "B3F-1000"))
      (libsource (lib "eagle-import") (part "10-XX"))
    )
    (comp (ref "S1-0C")
      (value "10-XX")
      (footprint "eagle-import:B3F-10XX")
      (fields (field (name "MPN") "B3F-1000"))
      (libsource (lib "eagle-import") (part "10-XX"))
    )
    (comp (ref "S1-P")
      (value "EG1218S")
      (footprint "eagle-import:EG1218")
      (libsource (lib "eagle-import") (part "EG1218S"))
    )
    (comp (ref "U0-C")
      (value "STM32F429ZIT6")
      (footprint "eagle-import:QFP50P2200X2200X160-144N")
      (fields (field (name "MOUSER_PART_NUMBER") "511-STM32F429ZIT6"))
      (libsource (lib "eagle-import") (part "STM32F429ZIT6"))
    )
    (comp (ref "U0-S")
      (value "TPS62202")
      (footprint "eagle-import:SOT95P280X145-5")
      (libsource (lib "eagle-import") (part "TPS62202"))
    )
    (comp (ref "U1-C")
      (value "TC58CVG2S0HRAIJ")
      (footprint "eagle-import:SON127P800X600X80-9N")
      (fields (field (name "MOUSER_PART_NUMBER") "757-TC58CVG2S0HRAIJ"))
      (libsource (lib "eagle-import") (part "TC58CVG2S0HRAIJ"))
    )
    (comp (ref "U1-P")
      (value "MCP73831")
      (footprint "eagle-import:SOT95P270X145-5N")
      (fields
        (field (name "MANUFACTURER_PART_NUMBER") "MCP73831T-2ACI/OT")
        (field (name "MOUSER_PART_NUMBER") "579-MCP73831T-2ACIOT")
      )
      (libsource (lib "eagle-import") (part "MCP73831T-2ACI_OT"))
    )
    (comp (ref "U1-S")
      (value "ICM-20948")
      (footprint "eagle-import:QFN40P300X300X105-25T159X175")
      (libsource (lib "eagle-import") (part "ICM-20948"))
    )
    (comp (ref "U2-C")
      (value "ADS1015BQDGSRQ1")
      (footprint "eagle-import:SOP50P490X110-10N")
      (fields (field (name "MOUSER_PART_NUMBER") "595-ADS1015BQDGSRQ1"))
      (libsource (lib "eagle-import") (part "ADS1015BQDGSRQ1"))
    )
    (comp (ref "U2-P")
      (value "ISL91110IRAZ-T7A")
      (footprint "eagle-import:QFN50P400X400X100-21N")
      (libsource (lib "eagle-import") (part "ISL91110IRAZ-T7A"))
    )
    (comp (ref "U2-S")
      (value "MMA1211KEG")
      (footprint "eagle-import:SOIC127P1041X355-16N")
      (libsource (lib "eagle-import") (part "MMA1211KEG"))
    )
    (comp (ref "U3-S")
      (value "MS5607")
      (footprint "eagle-import:MS5607")
      (libsource (lib "eagle-import") (part "MS5607"))
    )
    (comp (ref "U4-S")
      (value "FGPMMOPA6H")
      (footprint "eagle-import:SOIC127P1800X470-20N")
      (libsource (lib "eagle-import") (part "FGPMMOPA6H"))
    )
    (comp (ref "U7-P")
      (value "LM293DR")
      (footprint "eagle-import:SOIC127P600X175-8N")
      (fields (field (name "MOUSER_PART_NUMBER") "595-LM293DR"))
      (libsource (lib "eagle-import") (part "LM293DR"))
    )
    (comp (ref "U8-P")
      (value "LM293DR")
      (footprint "eagle-import:SOIC127P600X175-8N")
      (fields (field (name "MOUSER_PART_NUMBER") "595-LM293DR"))
      (libsource (lib "eagle-import") (part "LM293DR"))
    )
    (comp (ref "U9-P")
      (value "LM3671-ADJ")
      (footprint "eagle-import:SOT95P280X145-5N")
      (fields
        (field (name "MANUFACTURER_PART_NUMBER") "LM3671MFX-ADJ/NOPB")
        (field (name "MOUSER_PART_NUMBER") "926-LM3671MFXADJNOPB")
      )
      (libsource (lib "eagle-import") (part "LM3671MFX-ADJ_NOPB"))
    )
    (comp (ref "U11-S")
      (value "SN74LV1T34")
      (footprint "eagle-import:SOT65P210X110-5")
      (libsource (lib "eagle-import") (part "SN74LV1T34"))
    )
    (comp (ref "U12-S")
      (value "SN74LV1T34")
      (footprint "eagle-import:SOT65P210X110-5")
      (libsource (lib "eagle-import") (part "SN74LV1T34"))
    )
    (comp (ref "U13-S")
      (value "SN74LV1T34")
      (footprint "eagle-import:SOT65P210X110-5")
      (libsource (lib "eagle-import") (part "SN74LV1T34"))
    )
    (comp (ref "U14-S")
      (value "SN74LV1T34")
      (footprint "eagle-import:SOT65P210X110-5")
      (libsource (lib "eagle-import") (part "SN74LV1T34"))
    )
    (comp (ref "VR1-LS1C")
      (value "TRIM_US-LI10")
      (footprint "eagle-import:LI10")
      (libsource (lib "eagle-import") (part "TRIM_US-LI10"))
    )
    (comp (ref "Y1-C")
      (value "NX3225GD-8MHZ-STD-CRA-3")
      (footprint "eagle-import:3.2X2.5_KX-7")
      (libsource (lib "eagle-import") (part "KX-7"))
    )
  )
  (nets
    (net (code "13") (name "/EX_ANT") (class "Default")
      (node (ref "AT1-S") (pin "1") (pinfunction "SIGNAL_1") (pintype "bidirectional"))
      (node (ref "U4-S") (pin "11") (pinfunction "EX_ANT_11") (pintype "bidirectional"))
    )
    (net (code "20") (name "1V8") (class "Default")
      (node (ref "C2-0S") (pin "1") (pinfunction "1_1") (pintype "passive"))
      (node (ref "C2-1S") (pin "1") (pinfunction "1_1") (pintype "passive"))
      (node (ref "C3-1S") (pin "1") (pinfunction "1_1") (pintype "passive"))
      (node (ref "D1-1S") (pin "A") (pinfunction "A_A") (pintype "passive"))
      (node (ref "L1-0S") (pin "P$2") (pinfunction "2_P$2") (pintype "passive"))
      (node (ref "U0-S") (pin "4") (pinfunction "FB_4") (pintype "bidirectional"))
      (node (ref "U1-S") (pin "13") (pinfunction "VDD_13") (pintype "bidirectional"))
      (node (ref "U1-S") (pin "8") (pinfunction "VDDIO_8") (pintype "bidirectional"))
      (node (ref "U12-S") (pin "5") (pinfunction "VCC_5") (pintype "bidirectional"))
      (node (ref "U13-S") (pin "5") (pinfunction "VCC_5") (pintype "bidirectional"))
      (node (ref "U14-S") (pin "5") (pinfunction "VCC_5") (pintype "bidirectional"))
    )
    (net (code "21") (name "3D-FIX") (class "Default")
      (node (ref "D3-4S") (pin "A") (pinfunction "A_A") (pintype "passive"))
      (node (ref "U4-S") (pin "5") (pinfunction "3D-FIX_5") (pintype "bidirectional"))
    )
    (net (code "22") (name "3V3") (class "Default")
      (node (ref "C1-0C") (pin "1") (pinfunction "1_1") (pintype "passive"))
      (node (ref "C1-0S") (pin "1") (pinfunction "1_1") (pintype "passive"))
      (node (ref "C1-2C") (pin "1") (pinfunction "1_1") (pintype "passive"))
      (node (ref "C1-3S") (pin "1") (pinfunction "1_1") (pintype "passive"))
      (node (ref "C1-9P") (pin "1") (pinfunction "1_1") (pintype "passive"))
      (node (ref "C1-C") (pin "1") (pinfunction "1_1") (pintype "passive"))
      (node (ref "C10-0C") (pin "1") (pinfunction "1_1") (pintype "passive"))
      (node (ref "C11-0C") (pin "1") (pinfunction "1_1") (pintype "passive"))
      (node (ref "C12-0C") (pin "1") (pinfunction "1_1") (pintype "passive"))
      (node (ref "C13-0C") (pin "1") (pinfunction "1_1") (pintype "passive"))
      (node (ref "C14-0C") (pin "1") (pinfunction "1_1") (pintype "passive"))
      (node (ref "C2-0C") (pin "1") (pinfunction "1_1") (pintype "passive"))
      (node (ref "C3-0C") (pin "1") (pinfunction "1_1") (pintype "passive"))
      (node (ref "C4-0C") (pin "1") (pinfunction "1_1") (pintype "passive"))
      (node (ref "C4-9P") (pin "1") (pinfunction "1_1") (pintype "passive"))
      (node (ref "C5-0C") (pin "1") (pinfunction "1_1") (pintype "passive"))
      (node (ref "C6-0C") (pin "1") (pinfunction "1_1") (pintype "passive"))
      (node (ref "C7-0C") (pin "1") (pinfunction "1_1") (pintype "passive"))
      (node (ref "C8-0C") (pin "1") (pinfunction "1_1") (pintype "passive"))
      (node (ref "C9-0C") (pin "1") (pinfunction "1_1") (pintype "passive"))
      (node (ref "D1-2S") (pin "A") (pinfunction "A_A") (pintype "passive"))
      (node (ref "D1-3S") (pin "A") (pinfunction "A_A") (pintype "passive"))
      (node (ref "D1-4S") (pin "A") (pinfunction "A_A") (pintype "passive"))
      (node (ref "FB1-0C") (pin "1") (pinfunction "1_1") (pintype "bidirectional"))
      (node (ref "J1-C") (pin "4") (pinfunction "4_4") (pintype "passive"))
      (node (ref "JP-CP") (pin "1") (pinfunction "1_1") (pintype "passive"))
      (node (ref "JP-CS") (pin "1") (pinfunction "1_1") (pintype "passive"))
      (node (ref "L1-9P") (pin "2") (pinfunction "2_2") (pintype "bidirectional"))
      (node (ref "R1-2C") (pin "1") (pinfunction "1_1") (pintype "passive"))
      (node (ref "R1-9P") (pin "2") (pinfunction "2_2") (pintype "passive"))
      (node (ref "R2-2C") (pin "1") (pinfunction "1_1") (pintype "passive"))
      (node (ref "R3-9P") (pin "2") (pinfunction "2_2") (pintype "passive"))
      (node (ref "R3-J2C") (pin "2") (pinfunction "2_2") (pintype "passive"))
      (node (ref "R4-2C") (pin "1") (pinfunction "1_1") (pintype "passive"))
      (node (ref "S0-0C") (pin "1") (pinfunction "S_1") (pintype "passive"))
      (node (ref "U0-C") (pin "108") (pinfunction "VDD_9_108") (pintype "power_in"))
      (node (ref "U0-C") (pin "121") (pinfunction "VDD_10_121") (pintype "power_in"))
      (node (ref "U0-C") (pin "131") (pinfunction "VDD_11_131") (pintype "power_in"))
      (node (ref "U0-C") (pin "143") (pinfunction "PDR_ON_143") (pintype "bidirectional"))
      (node (ref "U0-C") (pin "144") (pinfunction "VDD_12_144") (pintype "power_in"))
      (node (ref "U0-C") (pin "17") (pinfunction "VDD_1_17") (pintype "power_in"))
      (node (ref "U0-C") (pin "30") (pinfunction "VDD_2_30") (pintype "power_in"))
      (node (ref "U0-C") (pin "39") (pinfunction "VDD_3_39") (pintype "power_in"))
      (node (ref "U0-C") (pin "52") (pinfunction "VDD_4_52") (pintype "power_in"))
      (node (ref "U0-C") (pin "6") (pinfunction "VBAT_6") (pintype "bidirectional"))
      (node (ref "U0-C") (pin "62") (pinfunction "VDD_5_62") (pintype "power_in"))
      (node (ref "U0-C") (pin "72") (pinfunction "VDD_6_72") (pintype "power_in"))
      (node (ref "U0-C") (pin "84") (pinfunction "VDD_7_84") (pintype "power_in"))
      (node (ref "U0-C") (pin "95") (pinfunction "VDD_8_95") (pintype "power_in"))
      (node (ref "U0-S") (pin "1") (pinfunction "VI_1") (pintype "bidirectional"))
      (node (ref "U0-S") (pin "3") (pinfunction "EN_3") (pintype "bidirectional"))
      (node (ref "U1-C") (pin "7") (pinfunction "VCC_7") (pintype "bidirectional"))
      (node (ref "U11-S") (pin "5") (pinfunction "VCC_5") (pintype "bidirectional"))
      (node (ref "U2-C") (pin "8") (pinfunction "VDD_8") (pintype "bidirectional"))
      (node (ref "U3-S") (pin "P$1") (pinfunction "VDD_P$1") (pintype "bidirectional"))
      (node (ref "U4-S") (pin "1") (pinfunction "VCC_1") (pintype "bidirectional"))
      (node (ref "U7-P") (pin "8") (pinfunction "VCC_8") (pintype "bidirectional"))
      (node (ref "U8-P") (pin "8") (pinfunction "VCC_8") (pintype "bidirectional"))
    )
    (net (code "23") (name "5V") (class "Default")
      (node (ref "C2-2S") (pin "1") (pinfunction "1_1") (pintype "passive"))
      (node (ref "C3-2P") (pin "1") (pinfunction "1_1") (pintype "passive"))
      (node (ref "C3-9P") (pin "1") (pinfunction "1_1") (pintype "passive"))
      (node (ref "C4-2P") (pin "1") (pinfunction "1_1") (pintype "passive"))
      (node (ref "C5-2P") (pin "1") (pinfunction "1_1") (pintype "passive"))
      (node (ref "J1-9P") (pin "14") (pinfunction "14_14") (pintype "passive"))
      (node (ref "JP-CP") (pin "2") (pinfunction "2_2") (pintype "passive"))
      (node (ref "JP-CS") (pin "2") (pinfunction "2_2") (pintype "passive"))
      (node (ref "R1-2P") (pin "2") (pinfunction "2_2") (pintype "passive"))
      (node (ref "U2-P") (pin "17") (pinfunction "VOUT_1_17") (pintype "bidirectional"))
      (node (ref "U2-P") (pin "18") (pinfunction "VOUT_2_18") (pintype "bidirectional"))
      (node (ref "U2-P") (pin "19") (pinfunction "VOUT_3_19") (pintype "bidirectional"))
      (node (ref "U2-P") (pin "20") (pinfunction "VOUT_4_20") (pintype "bidirectional"))
      (node (ref "U2-S") (pin "8") (pinfunction "VDD_8") (pintype "bidirectional"))
      (node (ref "U9-P") (pin "1") (pinfunction "VIN_1") (pintype "bidirectional"))
      (node (ref "U9-P") (pin "3") (pinfunction "EN_3") (pintype "bidirectional"))
      (node (ref "VR1-LS1C") (pin "A") (pinfunction "A_A") (pintype "passive"))
    )
    (net (code "24") (name "ACCEL_ANALOG") (class "Default")
      (node (ref "C1-2S") (pin "1") (pinfunction "1_1") (pintype "passive"))
      (node (ref "JP-CS") (pin "5") (pinfunction "5_5") (pintype "passive"))
      (node (ref "R3-2S") (pin "2") (pinfunction "2_2") (pintype "passive"))
      (node (ref "U0-C") (pin "46") (pinfunction "PB0_46") (pintype "bidirectional"))
    )
    (net (code "25") (name "ADC-ERROR") (class "Default")
      (node (ref "D6-C") (pin "A") (pinfunction "A_A") (pintype "passive"))
      (node (ref "U0-C") (pin "59") (pinfunction "PE8_59") (pintype "bidirectional"))
    )
    (net (code "26") (name "ADC_ALERT") (class "Default")
      (node (ref "R4-2C") (pin "2") (pinfunction "2_2") (pintype "passive"))
      (node (ref "U0-C") (pin "98") (pinfunction "PC8_98") (pintype "bidirectional"))
      (node (ref "U2-C") (pin "2") (pinfunction "ALERT/RDY_2") (pintype "bidirectional"))
    )
    (net (code "27") (name "ARMED-LED") (class "Default")
      (node (ref "D0A-C") (pin "A") (pinfunction "A_A") (pintype "passive"))
      (node (ref "D0B-C") (pin "A") (pinfunction "A_A") (pintype "passive"))
      (node (ref "D0C-C") (pin "A") (pinfunction "A_A") (pintype "passive"))
      (node (ref "U0-C") (pin "53") (pinfunction "PF13_53") (pintype "bidirectional"))
    )
    (net (code "28") (name "BATT_MEAS") (class "Default")
      (node (ref "JP-CP") (pin "5") (pinfunction "5_5") (pintype "passive"))
      (node (ref "R3-11P") (pin "1") (pinfunction "1_1") (pintype "passive"))
      (node (ref "R4-11P") (pin "2") (pinfunction "2_2") (pintype "passive"))
      (node (ref "U0-C") (pin "47") (pinfunction "PB1_47") (pintype "bidirectional"))
    )
    (net (code "29") (name "BUZZER_OUT") (class "Default")
      (node (ref "R1-LS1C") (pin "1") (pinfunction "1_1") (pintype "passive"))
      (node (ref "U0-C") (pin "1") (pinfunction "PE2_1") (pintype "bidirectional"))
    )
    (net (code "30") (name "CENTRAL-ERROR") (class "Default")
      (node (ref "D2A-C") (pin "A") (pinfunction "A_A") (pintype "passive"))
      (node (ref "D2B-C") (pin "A") (pinfunction "A_A") (pintype "passive"))
      (node (ref "U0-C") (pin "55") (pinfunction "PF15_55") (pintype "bidirectional"))
    )
    (net (code "31") (name "CENTRAL-NOMINAL") (class "Default")
      (node (ref "D1A-C") (pin "A") (pinfunction "A_A") (pintype "passive"))
      (node (ref "D1B-C") (pin "A") (pinfunction "A_A") (pintype "passive"))
      (node (ref "U0-C") (pin "54") (pinfunction "PF14_54") (pintype "bidirectional"))
    )
    (net (code "32") (name "CLK-1") (class "Default")
      (node (ref "J2-CS") (pin "1") (pinfunction "1_1") (pintype "passive"))
      (node (ref "U0-C") (pin "41") (pinfunction "PA5_41") (pintype "bidirectional"))
      (node (ref "U13-S") (pin "2") (pinfunction "A_2") (pintype "bidirectional"))
      (node (ref "U3-S") (pin "P$8") (pinfunction "SCLK_P$8") (pintype "bidirectional"))
    )
    (net (code "33") (name "CLK-1V8") (class "Default")
      (node (ref "U1-S") (pin "23") (pinfunction "SCL/SCLK_23") (pintype "bidirectional"))
      (node (ref "U13-S") (pin "4") (pinfunction "Y_4") (pintype "bidirectional"))
    )
    (net (code "34") (name "CLK-3") (class "Default")
      (node (ref "U0-C") (pin "111") (pinfunction "PC10_111") (pintype "bidirectional"))
      (node (ref "U1-C") (pin "6") (pinfunction "SCK_6") (pintype "bidirectional"))
    )
    (net (code "35") (name "CMP_LDO_IN") (class "Default")
      (node (ref "R1-11P") (pin "1") (pinfunction "1_1") (pintype "passive"))
      (node (ref "R2-11P") (pin "2") (pinfunction "2_2") (pintype "passive"))
      (node (ref "U7-P") (pin "3") (pinfunction "1IN+_3") (pintype "bidirectional"))
      (node (ref "U7-P") (pin "5") (pinfunction "2IN+_5") (pintype "bidirectional"))
      (node (ref "U8-P") (pin "3") (pinfunction "1IN+_3") (pintype "bidirectional"))
      (node (ref "U8-P") (pin "5") (pinfunction "2IN+_5") (pintype "bidirectional"))
    )
    (net (code "36") (name "CMP_LDO_OUT_1") (class "Default")
      (node (ref "Q1-5P") (pin "2") (pinfunction "G1_2") (pintype "bidirectional"))
      (node (ref "R2-5P") (pin "2") (pinfunction "2_2") (pintype "passive"))
      (node (ref "U7-P") (pin "1") (pinfunction "1OUT_1") (pintype "bidirectional"))
    )
    (net (code "37") (name "CMP_LDO_OUT_2") (class "Default")
      (node (ref "Q1-5P") (pin "4") (pinfunction "G2_4") (pintype "bidirectional"))
      (node (ref "R6-5P") (pin "2") (pinfunction "2_2") (pintype "passive"))
      (node (ref "U7-P") (pin "7") (pinfunction "2OUT_7") (pintype "bidirectional"))
    )
    (net (code "38") (name "CMP_LDO_OUT_3") (class "Default")
      (node (ref "Q1-6P") (pin "2") (pinfunction "G1_2") (pintype "bidirectional"))
      (node (ref "R2-6P") (pin "2") (pinfunction "2_2") (pintype "passive"))
      (node (ref "U8-P") (pin "1") (pinfunction "1OUT_1") (pintype "bidirectional"))
    )
    (net (code "39") (name "CMP_LDO_OUT_4") (class "Default")
      (node (ref "Q1-6P") (pin "4") (pinfunction "G2_4") (pintype "bidirectional"))
      (node (ref "R6-6P") (pin "2") (pinfunction "2_2") (pintype "passive"))
      (node (ref "U8-P") (pin "7") (pinfunction "2OUT_7") (pintype "bidirectional"))
    )
    (net (code "40") (name "CMP_RAIL") (class "Default")
      (node (ref "R3-9P") (pin "1") (pinfunction "1_1") (pintype "passive"))
      (node (ref "R4-9P") (pin "2") (pinfunction "2_2") (pintype "passive"))
      (node (ref "U7-P") (pin "2") (pinfunction "1IN-_2") (pintype "bidirectional"))
      (node (ref "U7-P") (pin "6") (pinfunction "2IN-_6") (pintype "bidirectional"))
      (node (ref "U8-P") (pin "2") (pinfunction "1IN-_2") (pintype "bidirectional"))
      (node (ref "U8-P") (pin "6") (pinfunction "2IN-_6") (pintype "bidirectional"))
    )
    (net (code "41") (name "CS-3") (class "Default")
      (node (ref "U0-C") (pin "114") (pinfunction "PD0_114") (pintype "bidirectional"))
      (node (ref "U1-C") (pin "1") (pinfunction "~{CS}_1") (pintype "bidirectional"))
    )
    (net (code "42") (name "CS1") (class "Default")
      (node (ref "J2-CS") (pin "4") (pinfunction "4_4") (pintype "passive"))
      (node (ref "U0-C") (pin "44") (pinfunction "PC4_44") (pintype "bidirectional"))
      (node (ref "U14-S") (pin "2") (pinfunction "A_2") (pintype "bidirectional"))
    )
    (net (code "43") (name "CS1-1V8") (class "Default")
      (node (ref "U1-S") (pin "22") (pinfunction "NCS_22") (pintype "bidirectional"))
      (node (ref "U14-S") (pin "4") (pinfunction "Y_4") (pintype "bidirectional"))
    )
    (net (code "44") (name "CS2") (class "Default")
      (node (ref "J2-CS") (pin "5") (pinfunction "5_5") (pintype "passive"))
      (node (ref "U0-C") (pin "45") (pinfunction "PC5_45") (pintype "bidirectional"))
      (node (ref "U3-S") (pin "P$4") (pinfunction "CSB_P$4") (pintype "bidirectional"))
      (node (ref "U3-S") (pin "P$5") (pinfunction "CSB_P$5") (pintype "bidirectional"))
    )
    (net (code "46") (name "CTS") (class "Default")
      (node (ref "J1-9P") (pin "13") (pinfunction "13_13") (pintype "passive"))
      (node (ref "J1-CP") (pin "4") (pinfunction "4_4") (pintype "passive"))
      (node (ref "U0-C") (pin "34") (pinfunction "PA0_34") (pintype "bidirectional"))
    )
    (net (code "47") (name "D+") (class "Default")
      (node (ref "R2-J2C") (pin "2") (pinfunction "2_2") (pintype "passive"))
      (node (ref "R3-J2C") (pin "1") (pinfunction "1_1") (pintype "passive"))
      (node (ref "U0-C") (pin "104") (pinfunction "PA12_104") (pintype "bidirectional"))
    )
    (net (code "48") (name "D-") (class "Default")
      (node (ref "R1-J2C") (pin "2") (pinfunction "2_2") (pintype "passive"))
      (node (ref "U0-C") (pin "103") (pinfunction "PA11_103") (pintype "bidirectional"))
    )
    (net (code "49") (name "DISARM_INPUT") (class "Default")
      (node (ref "R0-0C") (pin "2") (pinfunction "2_2") (pintype "passive"))
      (node (ref "S0-0C") (pin "3") (pinfunction "P_3") (pintype "passive"))
      (node (ref "U0-C") (pin "89") (pinfunction "PG4_89") (pintype "bidirectional"))
    )
    (net (code "50") (name "DROGUE-LED") (class "Default")
      (node (ref "D3-C") (pin "A") (pinfunction "A_A") (pintype "passive"))
      (node (ref "U0-C") (pin "56") (pinfunction "PG0_56") (pintype "bidirectional"))
    )
    (net (code "51") (name "FET_A") (class "Default")
      (node (ref "J2-P") (pin "2") (pinfunction "2_2") (pintype "bidirectional"))
      (node (ref "Q1-5P") (pin "7") (pinfunction "D1_1_7") (pintype "bidirectional"))
      (node (ref "Q1-5P") (pin "8") (pinfunction "D1_2_8") (pintype "bidirectional"))
      (node (ref "R3-5P") (pin "1") (pinfunction "1_1") (pintype "passive"))
    )
    (net (code "52") (name "FET_B") (class "Default")
      (node (ref "J2-P") (pin "4") (pinfunction "4_4") (pintype "bidirectional"))
      (node (ref "Q1-5P") (pin "5") (pinfunction "D2_1_5") (pintype "bidirectional"))
      (node (ref "Q1-5P") (pin "6") (pinfunction "D2_2_6") (pintype "bidirectional"))
      (node (ref "R7-5P") (pin "1") (pinfunction "1_1") (pintype "passive"))
    )
    (net (code "53") (name "FET_C") (class "Default")
      (node (ref "J2-P") (pin "6") (pinfunction "6_6") (pintype "bidirectional"))
      (node (ref "Q1-6P") (pin "7") (pinfunction "D1_1_7") (pintype "bidirectional"))
      (node (ref "Q1-6P") (pin "8") (pinfunction "D1_2_8") (pintype "bidirectional"))
      (node (ref "R3-6P") (pin "1") (pinfunction "1_1") (pintype "passive"))
    )
    (net (code "54") (name "FET_D") (class "Default")
      (node (ref "J2-P") (pin "8") (pinfunction "8_8") (pintype "bidirectional"))
      (node (ref "Q1-6P") (pin "5") (pinfunction "D2_1_5") (pintype "bidirectional"))
      (node (ref "Q1-6P") (pin "6") (pinfunction "D2_2_6") (pintype "bidirectional"))
      (node (ref "R7-6P") (pin "1") (pinfunction "1_1") (pintype "passive"))
    )
    (net (code "55") (name "FIRE_A") (class "Default")
      (node (ref "J2-CP") (pin "1") (pinfunction "1_1") (pintype "passive"))
      (node (ref "R1-5P") (pin "2") (pinfunction "2_2") (pintype "passive"))
      (node (ref "R2-5P") (pin "1") (pinfunction "1_1") (pintype "passive"))
      (node (ref "U0-C") (pin "11") (pinfunction "PF1_11") (pintype "bidirectional"))
    )
    (net (code "56") (name "FIRE_B") (class "Default")
      (node (ref "J2-CP") (pin "2") (pinfunction "2_2") (pintype "passive"))
      (node (ref "R5-5P") (pin "2") (pinfunction "2_2") (pintype "passive"))
      (node (ref "R6-5P") (pin "1") (pinfunction "1_1") (pintype "passive"))
      (node (ref "U0-C") (pin "12") (pinfunction "PF2_12") (pintype "bidirectional"))
    )
    (net (code "57") (name "FIRE_C") (class "Default")
      (node (ref "J2-CP") (pin "3") (pinfunction "3_3") (pintype "passive"))
      (node (ref "R1-6P") (pin "2") (pinfunction "2_2") (pintype "passive"))
      (node (ref "R2-6P") (pin "1") (pinfunction "1_1") (pintype "passive"))
      (node (ref "U0-C") (pin "13") (pinfunction "PF3_13") (pintype "bidirectional"))
    )
    (net (code "58") (name "FIRE_D") (class "Default")
      (node (ref "J2-CP") (pin "4") (pinfunction "4_4") (pintype "passive"))
      (node (ref "R5-6P") (pin "2") (pinfunction "2_2") (pintype "passive"))
      (node (ref "R6-6P") (pin "1") (pinfunction "1_1") (pintype "passive"))
      (node (ref "U0-C") (pin "14") (pinfunction "PF4_14") (pintype "bidirectional"))
    )
    (net (code "59") (name "GND") (class "Default")
      (node (ref "1S_LIPO") (pin "2") (pinfunction "2_2") (pintype "bidirectional"))
      (node (ref "AT1-S") (pin "2") (pinfunction "GND_1_2") (pintype "bidirectional"))
      (node (ref "AT1-S") (pin "3") (pinfunction "GND_2_3") (pintype "bidirectional"))
      (node (ref "AT1-S") (pin "4") (pinfunction "GND_3_4") (pintype "bidirectional"))
      (node (ref "C1") (pin "2") (pinfunction "2_2") (pintype "passive"))
      (node (ref "C1-0C") (pin "2") (pinfunction "2_2") (pintype "passive"))
      (node (ref "C1-0S") (pin "2") (pinfunction "2_2") (pintype "passive"))
      (node (ref "C1-11P") (pin "2") (pinfunction "2_2") (pintype "passive"))
      (node (ref "C1-1P") (pin "2") (pinfunction "2_2") (pintype "passive"))
      (node (ref "C1-1S") (pin "2") (pinfunction "2_2") (pintype "passive"))
      (node (ref "C1-2C") (pin "2") (pinfunction "2_2") (pintype "passive"))
      (node (ref "C1-2P") (pin "2") (pinfunction "2_2") (pintype "passive"))
      (node (ref "C1-2S") (pin "2") (pinfunction "2_2") (pintype "passive"))
      (node (ref "C1-3S") (pin "2") (pinfunction "2_2") (pintype "passive"))
      (node (ref "C1-C") (pin "2") (pinfunction "2_2") (pintype "passive"))
      (node (ref "C10-0C") (pin "2") (pinfunction "2_2") (pintype "passive"))
      (node (ref "C11-0C") (pin "2") (pinfunction "2_2") (pintype "passive"))
      (node (ref "C12-0C") (pin "2") (pinfunction "2_2") (pintype "passive"))
      (node (ref "C13-0C") (pin "2") (pinfunction "2_2") (pintype "passive"))
      (node (ref "C14-0C") (pin "2") (pinfunction "2_2") (pintype "passive"))
      (node (ref "C15-0C") (pin "2") (pinfunction "2_2") (pintype "passive"))
      (node (ref "C16-0C") (pin "2") (pinfunction "2_2") (pintype "passive"))
      (node (ref "C17-0C") (pin "2") (pinfunction "2_2") (pintype "passive"))
      (node (ref "C2") (pin "2") (pinfunction "2_2") (pintype "passive"))
      (node (ref "C2-0C") (pin "2") (pinfunction "2_2") (pintype "passive"))
      (node (ref "C2-0S") (pin "2") (pinfunction "2_2") (pintype "passive"))
      (node (ref "C2-1P") (pin "2") (pinfunction "2_2") (pintype "passive"))
      (node (ref "C2-1S") (pin "2") (pinfunction "2_2") (pintype "passive"))
      (node (ref "C2-2P") (pin "2") (pinfunction "2_2") (pintype "passive"))
      (node (ref "C2-2S") (pin "2") (pinfunction "2_2") (pintype "passive"))
      (node (ref "C2-9P") (pin "2") (pinfunction "2_2") (pintype "passive"))
      (node (ref "C3-0C") (pin "2") (pinfunction "2_2") (pintype "passive"))
      (node (ref "C3-1S") (pin "2") (pinfunction "2_2") (pintype "passive"))
      (node (ref "C3-9P") (pin "2") (pinfunction "2_2") (pintype "passive"))
      (node (ref "C4-0C") (pin "2") (pinfunction "2_2") (pintype "passive"))
      (node (ref "C4-2P") (pin "2") (pinfunction "2_2") (pintype "passive"))
      (node (ref "C4-9P") (pin "2") (pinfunction "2_2") (pintype "passive"))
      (node (ref "C5-0C") (pin "2") (pinfunction "2_2") (pintype "passive"))
      (node (ref "C5-2P") (pin "2") (pinfunction "2_2") (pintype "passive"))
      (node (ref "C6-0C") (pin "2") (pinfunction "2_2") (pintype "passive"))
      (node (ref "C7-0C") (pin "2") (pinfunction "2_2") (pintype "passive"))
      (node (ref "C8-0C") (pin "2") (pinfunction "2_2") (pintype "passive"))
      (node (ref "C9-0C") (pin "2") (pinfunction "2_2") (pintype "passive"))
      (node (ref "J1-9P") (pin "15") (pinfunction "15_15") (pintype "passive"))
      (node (ref "J1-C") (pin "1") (pinfunction "1_1") (pintype "passive"))
      (node (ref "J2-C") (pin "5") (pinfunction "GND_5") (pintype "power_in"))
      (node (ref "J2-C") (pin "S1") (pinfunction "SHIELD_S1") (pintype "power_in"))
      (node (ref "J2-C") (pin "S2") (pinfunction "SHIELD_S2") (pintype "power_in"))
      (node (ref "J2-C") (pin "S3") (pinfunction "SHIELD_S3") (pintype "power_in"))
      (node (ref "J2-C") (pin "S4") (pinfunction "SHIELD_S4") (pintype "power_in"))
      (node (ref "JP-CP") (pin "3") (pinfunction "3_3") (pintype "passive"))
      (node (ref "JP-CS") (pin "3") (pinfunction "3_3") (pintype "passive"))
      (node (ref "LS1-C") (pin "V-") (pinfunction "V-_V-") (pintype "bidirectional"))
      (node (ref "Q1-5P") (pin "1") (pinfunction "S1_1") (pintype "bidirectional"))
      (node (ref "Q1-5P") (pin "3") (pinfunction "S2_3") (pintype "bidirectional"))
      (node (ref "Q1-6P") (pin "1") (pinfunction "S1_1") (pintype "bidirectional"))
      (node (ref "Q1-6P") (pin "3") (pinfunction "S2_3") (pintype "bidirectional"))
      (node (ref "R0-0C") (pin "1") (pinfunction "1_1") (pintype "passive"))
      (node (ref "R0A-C") (pin "2") (pinfunction "2_2") (pintype "passive"))
      (node (ref "R0B-C") (pin "2") (pinfunction "2_2") (pintype "passive"))
      (node (ref "R0C-C") (pin "2") (pinfunction "2_2") (pintype "passive"))
      (node (ref "R1-0C") (pin "2") (pinfunction "2_2") (pintype "passive"))
      (node (ref "R1-1S") (pin "2") (pinfunction "2_2") (pintype "passive"))
      (node (ref "R1-2S") (pin "2") (pinfunction "2_2") (pintype "passive"))
      (node (ref "R1-3S") (pin "2") (pinfunction "2_2") (pintype "passive"))
      (node (ref "R1-4S") (pin "2") (pinfunction "2_2") (pintype "passive"))
      (node (ref "R1-5P") (pin "1") (pinfunction "1_1") (pintype "passive"))
      (node (ref "R1-6P") (pin "1") (pinfunction "1_1") (pintype "passive"))
      (node (ref "R1A-C") (pin "2") (pinfunction "2_2") (pintype "passive"))
      (node (ref "R1A-S") (pin "2") (pinfunction "2_2") (pintype "passive"))
      (node (ref "R1B-C") (pin "2") (pinfunction "2_2") (pintype "passive"))
      (node (ref "R1B-S") (pin "2") (pinfunction "2_2") (pintype "passive"))
      (node (ref "R2-11P") (pin "1") (pinfunction "1_1") (pintype "passive"))
      (node (ref "R2-1P") (pin "1") (pinfunction "1_1") (pintype "passive"))
      (node (ref "R2-1S") (pin "2") (pinfunction "2_2") (pintype "passive"))
      (node (ref "R2-2P") (pin "1") (pinfunction "1_1") (pintype "passive"))
      (node (ref "R2-2S") (pin "2") (pinfunction "2_2") (pintype "passive"))
      (node (ref "R2-3S") (pin "2") (pinfunction "2_2") (pintype "passive"))
      (node (ref "R2-4S") (pin "2") (pinfunction "2_2") (pintype "passive"))
      (node (ref "R2-9P") (pin "1") (pinfunction "1_1") (pintype "passive"))
      (node (ref "R2A-C") (pin "2") (pinfunction "2_2") (pintype "passive"))
      (node (ref "R2A-S") (pin "2") (pinfunction "2_2") (pintype "passive"))
      (node (ref "R2B-C") (pin "2") (pinfunction "2_2") (pintype "passive"))
      (node (ref "R2B-S") (pin "2") (pinfunction "2_2") (pintype "passive"))
      (node (ref "R3-11P") (pin "2") (pinfunction "2_2") (pintype "passive"))
      (node (ref "R3-2C") (pin "1") (pinfunction "1_1") (pintype "passive"))
      (node (ref "R3-4S") (pin "2") (pinfunction "2_2") (pintype "passive"))
      (node (ref "R3-C") (pin "2") (pinfunction "2_2") (pintype "passive"))
      (node (ref "R3-LS1C") (pin "1") (pinfunction "1_1") (pintype "passive"))
      (node (ref "R4-5P") (pin "1") (pinfunction "1_1") (pintype "passive"))
      (node (ref "R4-6P") (pin "1") (pinfunction "1_1") (pintype "passive"))
      (node (ref "R4-9P") (pin "1") (pinfunction "1_1") (pintype "passive"))
      (node (ref "R4-C") (pin "2") (pinfunction "2_2") (pintype "passive"))
      (node (ref "R5-5P") (pin "1") (pinfunction "1_1") (pintype "passive"))
      (node (ref "R5-6P") (pin "1") (pinfunction "1_1") (pintype "passive"))
      (node (ref "R5-C") (pin "2") (pinfunction "2_2") (pintype "passive"))
      (node (ref "R6-C") (pin "2") (pinfunction "2_2") (pintype "passive"))
      (node (ref "R8-5P") (pin "1") (pinfunction "1_1") (pintype "passive"))
      (node (ref "R8-6P") (pin "1") (pinfunction "1_1") (pintype "passive"))
      (node (ref "S1-0C") (pin "3") (pinfunction "P_3") (pintype "passive"))
      (node (ref "S1-0C") (pin "4") (pinfunction "P1_4") (pintype "passive"))
      (node (ref "U0-C") (pin "107") (pinfunction "VSS_7_107") (pintype "power_in"))
      (node (ref "U0-C") (pin "120") (pinfunction "VSS_8_120") (pintype "power_in"))
      (node (ref "U0-C") (pin "130") (pinfunction "VSS_9_130") (pintype "power_in"))
      (node (ref "U0-C") (pin "16") (pinfunction "VSS_1_16") (pintype "power_in"))
      (node (ref "U0-C") (pin "31") (pinfunction "VSSA_31") (pintype "power_in"))
      (node (ref "U0-C") (pin "38") (pinfunction "VSS_2_38") (pintype "power_in"))
      (node (ref "U0-C") (pin "51") (pinfunction "VSS_3_51") (pintype "power_in"))
      (node (ref "U0-C") (pin "61") (pinfunction "VSS_4_61") (pintype "power_in"))
      (node (ref "U0-C") (pin "83") (pinfunction "VSS_5_83") (pintype "power_in"))
      (node (ref "U0-C") (pin "94") (pinfunction "VSS_6_94") (pintype "power_in"))
      (node (ref "U0-S") (pin "2") (pinfunction "GND_2") (pintype "bidirectional"))
      (node (ref "U1-C") (pin "8") (pinfunction "VSS_8") (pintype "bidirectional"))
      (node (ref "U1-P") (pin "2") (pinfunction "VSS_2") (pintype "power_in"))
      (node (ref "U1-S") (pin "18") (pinfunction "GND_18") (pintype "bidirectional"))
      (node (ref "U1-S") (pin "20") (pinfunction "RESV.GND_20") (pintype "bidirectional"))
      (node (ref "U11-S") (pin "3") (pinfunction "GND_3") (pintype "bidirectional"))
      (node (ref "U12-S") (pin "3") (pinfunction "GND_3") (pintype "bidirectional"))
      (node (ref "U13-S") (pin "3") (pinfunction "GND_3") (pintype "bidirectional"))
      (node (ref "U14-S") (pin "3") (pinfunction "GND_3") (pintype "bidirectional"))
      (node (ref "U2-C") (pin "3") (pinfunction "GND_3") (pintype "bidirectional"))
      (node (ref "U2-P") (pin "12") (pinfunction "MODE_12") (pintype "bidirectional"))
      (node (ref "U2-P") (pin "13") (pinfunction "SGND_1_13") (pintype "bidirectional"))
      (node (ref "U2-P") (pin "3") (pinfunction "PGND_3") (pintype "bidirectional"))
      (node (ref "U2-S") (pin "7") (pinfunction "VSS_7") (pintype "bidirectional"))
      (node (ref "U3-S") (pin "P$2") (pinfunction "PS_P$2") (pintype "bidirectional"))
      (node (ref "U3-S") (pin "P$3") (pinfunction "GND_P$3") (pintype "bidirectional"))
      (node (ref "U4-S") (pin "12") (pinfunction "GND_12") (pintype "bidirectional"))
      (node (ref "U4-S") (pin "19") (pinfunction "GND_19") (pintype "bidirectional"))
      (node (ref "U4-S") (pin "3") (pinfunction "GND_3") (pintype "bidirectional"))
      (node (ref "U4-S") (pin "8") (pinfunction "GND_8") (pintype "bidirectional"))
      (node (ref "U7-P") (pin "4") (pinfunction "GND_4") (pintype "bidirectional"))
      (node (ref "U8-P") (pin "4") (pinfunction "GND_4") (pintype "bidirectional"))
      (node (ref "U9-P") (pin "2") (pinfunction "GND_2") (pintype "bidirectional"))
    )
    (net (code "60") (name "HOLD") (class "Default")
      (node (ref "U0-C") (pin "77") (pinfunction "PD8_77") (pintype "bidirectional"))
      (node (ref "U1-C") (pin "5") (pinfunction "~{HOLD}/IO3_5") (pintype "bidirectional"))
    )
    (net (code "61") (name "ID") (class "Default")
      (node (ref "J2-C") (pin "4") (pinfunction "ID_4") (pintype "bidirectional"))
      (node (ref "U0-C") (pin "102") (pinfunction "PA10_102") (pintype "bidirectional"))
    )
    (net (code "62") (name "MAIN-LED") (class "Default")
      (node (ref "D4-C") (pin "A") (pinfunction "A_A") (pintype "passive"))
      (node (ref "U0-C") (pin "57") (pinfunction "PG1_57") (pintype "bidirectional"))
    )
    (net (code "63") (name "MASTER_RX-1") (class "Default")
      (node (ref "J1-CS") (pin "1") (pinfunction "1_1") (pintype "passive"))
      (node (ref "U0-C") (pin "97") (pinfunction "PC7_97") (pintype "bidirectional"))
      (node (ref "U4-S") (pin "9") (pinfunction "TX_9") (pintype "bidirectional"))
    )
    (net (code "64") (name "MASTER_RX-2") (class "Default")
      (node (ref "J1-9P") (pin "7") (pinfunction "7_7") (pintype "passive"))
      (node (ref "J1-CP") (pin "2") (pinfunction "2_2") (pintype "passive"))
      (node (ref "U0-C") (pin "37") (pinfunction "PA3_37") (pintype "bidirectional"))
    )
    (net (code "65") (name "MASTER_TX-1") (class "Default")
      (node (ref "J1-CS") (pin "2") (pinfunction "2_2") (pintype "passive"))
      (node (ref "U0-C") (pin "96") (pinfunction "PC6_96") (pintype "bidirectional"))
      (node (ref "U4-S") (pin "10") (pinfunction "RX_10") (pintype "bidirectional"))
    )
    (net (code "66") (name "MASTER_TX-2") (class "Default")
      (node (ref "J1-9P") (pin "9") (pinfunction "9_9") (pintype "passive"))
      (node (ref "J1-CP") (pin "3") (pinfunction "3_3") (pintype "passive"))
      (node (ref "U0-C") (pin "36") (pinfunction "PA2_36") (pintype "bidirectional"))
    )
    (net (code "67") (name "MISO-1") (class "Default")
      (node (ref "J2-CS") (pin "2") (pinfunction "2_2") (pintype "passive"))
      (node (ref "U0-C") (pin "42") (pinfunction "PA6_42") (pintype "bidirectional"))
      (node (ref "U11-S") (pin "4") (pinfunction "Y_4") (pintype "bidirectional"))
    )
    (net (code "68") (name "MISO-1V8") (class "Default")
      (node (ref "U1-S") (pin "9") (pinfunction "SDO/AD0_9") (pintype "bidirectional"))
      (node (ref "U11-S") (pin "2") (pinfunction "A_2") (pintype "bidirectional"))
    )
    (net (code "69") (name "MISO-3") (class "Default")
      (node (ref "U0-C") (pin "112") (pinfunction "PC11_112") (pintype "bidirectional"))
      (node (ref "U1-C") (pin "2") (pinfunction "SO/IO1_2") (pintype "bidirectional"))
    )
    (net (code "70") (name "MOSI-1") (class "Default")
      (node (ref "J2-CS") (pin "3") (pinfunction "3_3") (pintype "passive"))
      (node (ref "U0-C") (pin "43") (pinfunction "PA7_43") (pintype "bidirectional"))
      (node (ref "U12-S") (pin "2") (pinfunction "A_2") (pintype "bidirectional"))
      (node (ref "U3-S") (pin "P$6") (pinfunction "SDO_P$6") (pintype "bidirectional"))
      (node (ref "U3-S") (pin "P$7") (pinfunction "SDI_P$7") (pintype "bidirectional"))
    )
    (net (code "71") (name "MOSI-1V8") (class "Default")
      (node (ref "U1-S") (pin "24") (pinfunction "SDA/SDI_24") (pintype "bidirectional"))
      (node (ref "U12-S") (pin "4") (pinfunction "Y_4") (pintype "bidirectional"))
    )
    (net (code "72") (name "MOSI-3") (class "Default")
      (node (ref "U0-C") (pin "113") (pinfunction "PC12_113") (pintype "bidirectional"))
      (node (ref "U1-C") (pin "4") (pinfunction "SI/IO0_4") (pintype "bidirectional"))
    )
    (net (code "74") (name "NRST") (class "Default")
      (node (ref "C15-0C") (pin "1") (pinfunction "1_1") (pintype "passive"))
      (node (ref "R2-J1C") (pin "2") (pinfunction "2_2") (pintype "passive"))
      (node (ref "S1-0C") (pin "1") (pinfunction "S_1") (pintype "passive"))
      (node (ref "S1-0C") (pin "2") (pinfunction "S1_2") (pintype "passive"))
      (node (ref "U0-C") (pin "25") (pinfunction "NRST_25") (pintype "input"))
    )
    (net (code "75") (name "Net-(D0A-C-PadC)") (class "Default")
      (node (ref "D0A-C") (pin "C") (pinfunction "C_C") (pintype "passive"))
      (node (ref "R0A-C") (pin "1") (pinfunction "1_1") (pintype "passive"))
    )
    (net (code "76") (name "Net-(D0B-C-PadC)") (class "Default")
      (node (ref "D0B-C") (pin "C") (pinfunction "C_C") (pintype "passive"))
      (node (ref "R0B-C") (pin "1") (pinfunction "1_1") (pintype "passive"))
    )
    (net (code "77") (name "Net-(D0C-C-PadC)") (class "Default")
      (node (ref "D0C-C") (pin "C") (pinfunction "C_C") (pintype "passive"))
      (node (ref "R0C-C") (pin "1") (pinfunction "1_1") (pintype "passive"))
    )
    (net (code "78") (name "Net-(D1-1P-PadC)") (class "Default")
      (node (ref "D1-1P") (pin "C") (pinfunction "C_C") (pintype "passive"))
      (node (ref "R1-1P") (pin "1") (pinfunction "1_1") (pintype "passive"))
    )
    (net (code "79") (name "Net-(D1-1S-PadC)") (class "Default")
      (node (ref "D1-1S") (pin "C") (pinfunction "C_C") (pintype "passive"))
      (node (ref "R1-1S") (pin "1") (pinfunction "1_1") (pintype "passive"))
    )
    (net (code "80") (name "Net-(D1-2S-PadC)") (class "Default")
      (node (ref "D1-2S") (pin "C") (pinfunction "C_C") (pintype "passive"))
      (node (ref "R1-2S") (pin "1") (pinfunction "1_1") (pintype "passive"))
    )
    (net (code "81") (name "Net-(D1-3S-PadC)") (class "Default")
      (node (ref "D1-3S") (pin "C") (pinfunction "C_C") (pintype "passive"))
      (node (ref "R1-3S") (pin "1") (pinfunction "1_1") (pintype "passive"))
    )
    (net (code "82") (name "Net-(D1-4S-PadC)") (class "Default")
      (node (ref "D1-4S") (pin "C") (pinfunction "C_C") (pintype "passive"))
      (node (ref "R1-4S") (pin "1") (pinfunction "1_1") (pintype "passive"))
    )
    (net (code "83") (name "Net-(D1-11P-A)") (class "Default")
      (node (ref "D1-11P") (pin "2") (pinfunction "A_2") (pintype "bidirectional"))
      (node (ref "R4-11P") (pin "1") (pinfunction "1_1") (pintype "passive"))
      (node (ref "S1-P") (pin "S") (pinfunction "S_S") (pintype "passive"))
    )
    (net (code "84") (name "Net-(D1A-C-PadC)") (class "Default")
      (node (ref "D1A-C") (pin "C") (pinfunction "C_C") (pintype "passive"))
      (node (ref "R1A-C") (pin "1") (pinfunction "1_1") (pintype "passive"))
    )
    (net (code "85") (name "Net-(D1A-S-PadC)") (class "Default")
      (node (ref "D1A-S") (pin "C") (pinfunction "C_C") (pintype "passive"))
      (node (ref "R1A-S") (pin "1") (pinfunction "1_1") (pintype "passive"))
    )
    (net (code "86") (name "Net-(D1B-C-PadC)") (class "Default")
      (node (ref "D1B-C") (pin "C") (pinfunction "C_C") (pintype "passive"))
      (node (ref "R1B-C") (pin "1") (pinfunction "1_1") (pintype "passive"))
    )
    (net (code "87") (name "Net-(D1B-S-PadC)") (class "Default")
      (node (ref "D1B-S") (pin "C") (pinfunction "C_C") (pintype "passive"))
      (node (ref "R1B-S") (pin "1") (pinfunction "1_1") (pintype "passive"))
    )
    (net (code "88") (name "Net-(D2-1S-PadC)") (class "Default")
      (node (ref "D2-1S") (pin "C") (pinfunction "C_C") (pintype "passive"))
      (node (ref "R2-1S") (pin "1") (pinfunction "1_1") (pintype "passive"))
    )
    (net (code "89") (name "Net-(D2-2S-PadC)") (class "Default")
      (node (ref "D2-2S") (pin "C") (pinfunction "C_C") (pintype "passive"))
      (node (ref "R2-2S") (pin "1") (pinfunction "1_1") (pintype "passive"))
    )
    (net (code "90") (name "Net-(D2-3S-PadC)") (class "Default")
      (node (ref "D2-3S") (pin "C") (pinfunction "C_C") (pintype "passive"))
      (node (ref "R2-3S") (pin "1") (pinfunction "1_1") (pintype "passive"))
    )
    (net (code "91") (name "Net-(D2-4S-PadC)") (class "Default")
      (node (ref "D2-4S") (pin "C") (pinfunction "C_C") (pintype "passive"))
      (node (ref "R2-4S") (pin "1") (pinfunction "1_1") (pintype "passive"))
    )
    (net (code "92") (name "Net-(D2A-C-PadC)") (class "Default")
      (node (ref "D2A-C") (pin "C") (pinfunction "C_C") (pintype "passive"))
      (node (ref "R2A-C") (pin "1") (pinfunction "1_1") (pintype "passive"))
    )
    (net (code "93") (name "Net-(D2A-S-PadC)") (class "Default")
      (node (ref "D2A-S") (pin "C") (pinfunction "C_C") (pintype "passive"))
      (node (ref "R2A-S") (pin "1") (pinfunction "1_1") (pintype "passive"))
    )
    (net (code "94") (name "Net-(D2B-C-PadC)") (class "Default")
      (node (ref "D2B-C") (pin "C") (pinfunction "C_C") (pintype "passive"))
      (node (ref "R2B-C") (pin "1") (pinfunction "1_1") (pintype "passive"))
    )
    (net (code "95") (name "Net-(D2B-S-PadC)") (class "Default")
      (node (ref "D2B-S") (pin "C") (pinfunction "C_C") (pintype "passive"))
      (node (ref "R2B-S") (pin "1") (pinfunction "1_1") (pintype "passive"))
    )
    (net (code "96") (name "Net-(D3-4S-PadC)") (class "Default")
      (node (ref "D3-4S") (pin "C") (pinfunction "C_C") (pintype "passive"))
      (node (ref "R3-4S") (pin "1") (pinfunction "1_1") (pintype "passive"))
    )
    (net (code "97") (name "Net-(D3-C-PadC)") (class "Default")
      (node (ref "D3-C") (pin "C") (pinfunction "C_C") (pintype "passive"))
      (node (ref "R3-C") (pin "1") (pinfunction "1_1") (pintype "passive"))
    )
    (net (code "98") (name "Net-(D4-C-PadC)") (class "Default")
      (node (ref "D4-C") (pin "C") (pinfunction "C_C") (pintype "passive"))
      (node (ref "R4-C") (pin "1") (pinfunction "1_1") (pintype "passive"))
    )
    (net (code "99") (name "Net-(D5-C-PadC)") (class "Default")
      (node (ref "D5-C") (pin "C") (pinfunction "C_C") (pintype "passive"))
      (node (ref "R5-C") (pin "1") (pinfunction "1_1") (pintype "passive"))
    )
    (net (code "100") (name "Net-(D6-C-PadC)") (class "Default")
      (node (ref "D6-C") (pin "C") (pinfunction "C_C") (pintype "passive"))
      (node (ref "R6-C") (pin "1") (pinfunction "1_1") (pintype "passive"))
    )
    (net (code "101") (name "Net-(J1-C-Pad5)") (class "Default")
      (node (ref "J1-C") (pin "5") (pinfunction "5_5") (pintype "passive"))
      (node (ref "R1-J1C") (pin "1") (pinfunction "1_1") (pintype "passive"))
    )
    (net (code "102") (name "Net-(J1-C-Pad6)") (class "Default")
      (node (ref "J1-C") (pin "6") (pinfunction "6_6") (pintype "passive"))
      (node (ref "R2-J1C") (pin "1") (pinfunction "1_1") (pintype "passive"))
    )
    (net (code "103") (name "Net-(J2-C-D+)") (class "Default")
      (node (ref "J2-C") (pin "3") (pinfunction "D+_3") (pintype "bidirectional"))
      (node (ref "R2-J2C") (pin "1") (pinfunction "1_1") (pintype "passive"))
    )
    (net (code "104") (name "Net-(J2-C-D-)") (class "Default")
      (node (ref "J2-C") (pin "2") (pinfunction "D-_2") (pintype "bidirectional"))
      (node (ref "R1-J2C") (pin "1") (pinfunction "1_1") (pintype "passive"))
    )
    (net (code "105") (name "Net-(L1-0S-1)") (class "Default")
      (node (ref "L1-0S") (pin "P$1") (pinfunction "1_P$1") (pintype "passive"))
      (node (ref "U0-S") (pin "5") (pinfunction "SW_5") (pintype "bidirectional"))
    )
    (net (code "106") (name "Net-(LS1-C-PadV+)") (class "Default")
      (node (ref "LS1-C") (pin "V+") (pinfunction "V+_V+") (pintype "bidirectional"))
      (node (ref "R2-LS1C") (pin "1") (pinfunction "1_1") (pintype "passive"))
    )
    (net (code "107") (name "Net-(Q1-LS1C-B)") (class "Default")
      (node (ref "Q1-LS1C") (pin "1") (pinfunction "B_1") (pintype "passive"))
      (node (ref "R1-LS1C") (pin "2") (pinfunction "2_2") (pintype "passive"))
    )
    (net (code "108") (name "Net-(Q1-LS1C-C)") (class "Default")
      (node (ref "Q1-LS1C") (pin "2") (pinfunction "C_2") (pintype "passive"))
      (node (ref "VR1-LS1C") (pin "S") (pinfunction "S_S") (pintype "passive"))
    )
    (net (code "109") (name "Net-(Q1-LS1C-E)") (class "Default")
      (node (ref "Q1-LS1C") (pin "3") (pinfunction "E_3") (pintype "passive"))
      (node (ref "R2-LS1C") (pin "2") (pinfunction "2_2") (pintype "passive"))
    )
    (net (code "110") (name "Net-(R3-LS1C-Pad2)") (class "Default")
      (node (ref "R3-LS1C") (pin "2") (pinfunction "2_2") (pintype "passive"))
      (node (ref "VR1-LS1C") (pin "E") (pinfunction "E_E") (pintype "passive"))
    )
    (net (code "111") (name "Net-(U0-C-BOOT0)") (class "Default")
      (node (ref "R1-0C") (pin "1") (pinfunction "1_1") (pintype "passive"))
      (node (ref "U0-C") (pin "138") (pinfunction "BOOT0_138") (pintype "bidirectional"))
    )
    (net (code "112") (name "Net-(U0-C-VCAP_1)") (class "Default")
      (node (ref "C16-0C") (pin "1") (pinfunction "1_1") (pintype "passive"))
      (node (ref "U0-C") (pin "71") (pinfunction "VCAP_1_71") (pintype "bidirectional"))
    )
    (net (code "113") (name "Net-(U0-C-VCAP_2)") (class "Default")
      (node (ref "C17-0C") (pin "1") (pinfunction "1_1") (pintype "passive"))
      (node (ref "U0-C") (pin "106") (pinfunction "VCAP_2_106") (pintype "bidirectional"))
    )
    (net (code "114") (name "Net-(U1-P-PROG)") (class "Default")
      (node (ref "R2-1P") (pin "2") (pinfunction "2_2") (pintype "passive"))
      (node (ref "U1-P") (pin "5") (pinfunction "PROG_5") (pintype "bidirectional"))
    )
    (net (code "115") (name "Net-(U1-P-STAT)") (class "Default")
      (node (ref "R1-1P") (pin "2") (pinfunction "2_2") (pintype "passive"))
      (node (ref "U1-P") (pin "1") (pinfunction "STAT_1") (pintype "bidirectional"))
    )
    (net (code "116") (name "Net-(U1-S-REGOUT)") (class "Default")
      (node (ref "C1-1S") (pin "1") (pinfunction "1_1") (pintype "passive"))
      (node (ref "U1-S") (pin "10") (pinfunction "REGOUT_10") (pintype "bidirectional"))
    )
    (net (code "117") (name "Net-(U2-C-ADDR)") (class "Default")
      (node (ref "R3-2C") (pin "2") (pinfunction "2_2") (pintype "passive"))
      (node (ref "U2-C") (pin "1") (pinfunction "ADDR_1") (pintype "bidirectional"))
    )
    (net (code "118") (name "Net-(U2-P-LX1_1)") (class "Default")
      (node (ref "L1-2P") (pin "2") (pinfunction "2_2") (pintype "bidirectional"))
      (node (ref "U2-P") (pin "4") (pinfunction "LX1_1_4") (pintype "bidirectional"))
    )
    (net (code "119") (name "Net-(U2-P-LX2_1)") (class "Default")
      (node (ref "L1-2P") (pin "1") (pinfunction "1_1") (pintype "bidirectional"))
      (node (ref "U2-P") (pin "1") (pinfunction "LX2_1_1") (pintype "bidirectional"))
    )
    (net (code "120") (name "Net-(U2-S-VOUT)") (class "Default")
      (node (ref "R3-2S") (pin "1") (pinfunction "1_1") (pintype "passive"))
      (node (ref "U2-S") (pin "5") (pinfunction "VOUT_5") (pintype "bidirectional"))
    )
    (net (code "121") (name "OSC_IN") (class "Default")
      (node (ref "C1") (pin "1") (pinfunction "1_1") (pintype "passive"))
      (node (ref "U0-C") (pin "23") (pinfunction "PH0_23") (pintype "bidirectional"))
      (node (ref "Y1-C") (pin "3") (pinfunction "2_3") (pintype "passive"))
    )
    (net (code "122") (name "OSC_OUT") (class "Default")
      (node (ref "C2") (pin "1") (pinfunction "1_1") (pintype "passive"))
      (node (ref "U0-C") (pin "24") (pinfunction "PH1_24") (pintype "bidirectional"))
      (node (ref "Y1-C") (pin "1") (pinfunction "1_1") (pintype "passive"))
    )
    (net (code "123") (name "RTS") (class "Default")
      (node (ref "J1-9P") (pin "5") (pinfunction "5_5") (pintype "passive"))
      (node (ref "J1-CP") (pin "1") (pinfunction "1_1") (pintype "passive"))
      (node (ref "U0-C") (pin "35") (pinfunction "PA1_35") (pintype "bidirectional"))
    )
    (net (code "124") (name "SCL-1") (class "Default")
      (node (ref "R2-2C") (pin "2") (pinfunction "2_2") (pintype "passive"))
      (node (ref "U0-C") (pin "100") (pinfunction "PA8_100") (pintype "bidirectional"))
      (node (ref "U2-C") (pin "10") (pinfunction "SCL_10") (pintype "bidirectional"))
    )
    (net (code "125") (name "SDA-1") (class "Default")
      (node (ref "R1-2C") (pin "2") (pinfunction "2_2") (pintype "passive"))
      (node (ref "U0-C") (pin "99") (pinfunction "PC9_99") (pintype "bidirectional"))
      (node (ref "U2-C") (pin "9") (pinfunction "SDA_9") (pintype "bidirectional"))
    )
    (net (code "126") (name "SENSE_A") (class "Default")
      (node (ref "J3-CP") (pin "1") (pinfunction "1_1") (pintype "passive"))
      (node (ref "R3-5P") (pin "2") (pinfunction "2_2") (pintype "passive"))
      (node (ref "R4-5P") (pin "2") (pinfunction "2_2") (pintype "passive"))
      (node (ref "U0-C") (pin "18") (pinfunction "PF6_18") (pintype "bidirectional"))
      (node (ref "U2-C") (pin "4") (pinfunction "AIN0_4") (pintype "bidirectional"))
    )
    (net (code "127") (name "SENSE_B") (class "Default")
      (node (ref "J3-CP") (pin "2") (pinfunction "2_2") (pintype "passive"))
      (node (ref "R7-5P") (pin "2") (pinfunction "2_2") (pintype "passive"))
      (node (ref "R8-5P") (pin "2") (pinfunction "2_2") (pintype "passive"))
      (node (ref "U0-C") (pin "19") (pinfunction "PF7_19") (pintype "bidirectional"))
      (node (ref "U2-C") (pin "5") (pinfunction "AIN1_5") (pintype "bidirectional"))
    )
    (net (code "128") (name "SENSE_C") (class "Default")
      (node (ref "J3-CP") (pin "3") (pinfunction "3_3") (pintype "passive"))
      (node (ref "R3-6P") (pin "2") (pinfunction "2_2") (pintype "passive"))
      (node (ref "R4-6P") (pin "2") (pinfunction "2_2") (pintype "passive"))
      (node (ref "U0-C") (pin "20") (pinfunction "PF8_20") (pintype "bidirectional"))
      (node (ref "U2-C") (pin "6") (pinfunction "AIN2_6") (pintype "bidirectional"))
    )
    (net (code "129") (name "SENSE_D") (class "Default")
      (node (ref "J3-CP") (pin "4") (pinfunction "4_4") (pintype "passive"))
      (node (ref "R7-6P") (pin "2") (pinfunction "2_2") (pintype "passive"))
      (node (ref "R8-6P") (pin "2") (pinfunction "2_2") (pintype "passive"))
      (node (ref "U0-C") (pin "21") (pinfunction "PF9_21") (pintype "bidirectional"))
      (node (ref "U2-C") (pin "7") (pinfunction "AIN3_7") (pintype "bidirectional"))
    )
    (net (code "130") (name "SENSOR-ERROR") (class "Default")
      (node (ref "D2A-S") (pin "A") (pinfunction "A_A") (pintype "passive"))
      (node (ref "D2B-S") (pin "A") (pinfunction "A_A") (pintype "passive"))
      (node (ref "J3-CS") (pin "2") (pinfunction "2_2") (pintype "passive"))
      (node (ref "U0-C") (pin "64") (pinfunction "PE11_64") (pintype "bidirectional"))
    )
    (net (code "131") (name "SENSOR-NOMINAL") (class "Default")
      (node (ref "D1A-S") (pin "A") (pinfunction "A_A") (pintype "passive"))
      (node (ref "D1B-S") (pin "A") (pinfunction "A_A") (pintype "passive"))
      (node (ref "J3-CS") (pin "1") (pinfunction "1_1") (pintype "passive"))
      (node (ref "U0-C") (pin "63") (pinfunction "PE10_63") (pintype "bidirectional"))
    )
    (net (code "132") (name "STORAGE-ERROR") (class "Default")
      (node (ref "D5-C") (pin "A") (pinfunction "A_A") (pintype "passive"))
      (node (ref "U0-C") (pin "58") (pinfunction "PE7_58") (pintype "bidirectional"))
    )
    (net (code "133") (name "SWCLK") (class "Default")
      (node (ref "J1-C") (pin "2") (pinfunction "2_2") (pintype "passive"))
      (node (ref "R4-J1C") (pin "1") (pinfunction "1_1") (pintype "passive"))
      (node (ref "R4-J1C") (pin "2") (pinfunction "2_2") (pintype "passive"))
      (node (ref "U0-C") (pin "109") (pinfunction "PA14_109") (pintype "bidirectional"))
    )
    (net (code "134") (name "SWDIO") (class "Default")
      (node (ref "J1-C") (pin "3") (pinfunction "3_3") (pintype "passive"))
      (node (ref "R3-J1C") (pin "1") (pinfunction "1_1") (pintype "passive"))
      (node (ref "R3-J1C") (pin "2") (pinfunction "2_2") (pintype "passive"))
      (node (ref "U0-C") (pin "105") (pinfunction "PA13_105") (pintype "bidirectional"))
    )
    (net (code "135") (name "SWO") (class "Default")
      (node (ref "R1-J1C") (pin "2") (pinfunction "2_2") (pintype "passive"))
      (node (ref "U0-C") (pin "133") (pinfunction "PB3_133") (pintype "bidirectional"))
    )
    (net (code "136") (name "U1S-CHECK") (class "Default")
      (node (ref "D2-1S") (pin "A") (pinfunction "A_A") (pintype "passive"))
      (node (ref "J3-CS") (pin "3") (pinfunction "3_3") (pintype "passive"))
      (node (ref "U0-C") (pin "65") (pinfunction "PE12_65") (pintype "bidirectional"))
    )
    (net (code "137") (name "U2P-FB") (class "Default")
      (node (ref "C3-2P") (pin "2") (pinfunction "2_2") (pintype "passive"))
      (node (ref "R1-2P") (pin "1") (pinfunction "1_1") (pintype "passive"))
      (node (ref "R2-2P") (pin "2") (pinfunction "2_2") (pintype "passive"))
      (node (ref "U2-P") (pin "15") (pinfunction "FB_15") (pintype "bidirectional"))
    )
    (net (code "138") (name "U2S-CHECK") (class "Default")
      (node (ref "D2-2S") (pin "A") (pinfunction "A_A") (pintype "passive"))
      (node (ref "J3-CS") (pin "4") (pinfunction "4_4") (pintype "passive"))
      (node (ref "U0-C") (pin "66") (pinfunction "PE13_66") (pintype "bidirectional"))
    )
    (net (code "139") (name "U2S-ST") (class "Default")
      (node (ref "J3-CS") (pin "7") (pinfunction "7_7") (pintype "passive"))
      (node (ref "U0-C") (pin "69") (pinfunction "PB10_69") (pintype "bidirectional"))
      (node (ref "U2-S") (pin "4") (pinfunction "ST_4") (pintype "bidirectional"))
    )
    (net (code "141") (name "U3S-CHECK") (class "Default")
      (node (ref "D2-3S") (pin "A") (pinfunction "A_A") (pintype "passive"))
      (node (ref "J3-CS") (pin "5") (pinfunction "5_5") (pintype "passive"))
      (node (ref "U0-C") (pin "67") (pinfunction "PE14_67") (pintype "bidirectional"))
    )
    (net (code "143") (name "U4S-CHECK") (class "Default")
      (node (ref "D2-4S") (pin "A") (pinfunction "A_A") (pintype "passive"))
      (node (ref "J3-CS") (pin "6") (pinfunction "6_6") (pintype "passive"))
      (node (ref "U0-C") (pin "68") (pinfunction "PE15_68") (pintype "bidirectional"))
    )
    (net (code "144") (name "U9P-FB") (class "Default")
      (node (ref "C1-9P") (pin "2") (pinfunction "2_2") (pintype "passive"))
      (node (ref "C2-9P") (pin "1") (pinfunction "1_1") (pintype "passive"))
      (node (ref "R1-9P") (pin "1") (pinfunction "1_1") (pintype "passive"))
      (node (ref "R2-9P") (pin "2") (pinfunction "2_2") (pintype "passive"))
      (node (ref "U9-P") (pin "4") (pinfunction "FB_4") (pintype "bidirectional"))
    )
    (net (code "145") (name "U9P-SW") (class "Default")
      (node (ref "L1-9P") (pin "1") (pinfunction "1_1") (pintype "bidirectional"))
      (node (ref "U9-P") (pin "5") (pinfunction "SW_5") (pintype "bidirectional"))
    )
    (net (code "146") (name "US2-STATUS") (class "Default")
      (node (ref "J3-CS") (pin "8") (pinfunction "8_8") (pintype "passive"))
      (node (ref "U0-C") (pin "70") (pinfunction "PB11_70") (pintype "bidirectional"))
      (node (ref "U2-S") (pin "6") (pinfunction "STATUS_6") (pintype "bidirectional"))
    )
    (net (code "147") (name "VBAT") (class "Default")
      (node (ref "1S_LIPO") (pin "1") (pinfunction "1_1") (pintype "bidirectional"))
      (node (ref "C2-1P") (pin "1") (pinfunction "1_1") (pintype "passive"))
      (node (ref "J2-P") (pin "1") (pinfunction "1_1") (pintype "bidirectional"))
      (node (ref "J2-P") (pin "3") (pinfunction "3_3") (pintype "bidirectional"))
      (node (ref "J2-P") (pin "5") (pinfunction "5_5") (pintype "bidirectional"))
      (node (ref "J2-P") (pin "7") (pinfunction "7_7") (pintype "bidirectional"))
      (node (ref "S1-P") (pin "P") (pinfunction "P_P") (pintype "passive"))
      (node (ref "U1-P") (pin "3") (pinfunction "VBAT_3") (pintype "bidirectional"))
    )
    (net (code "148") (name "VDDA") (class "Default")
      (node (ref "FB1-0C") (pin "2") (pinfunction "2_2") (pintype "bidirectional"))
      (node (ref "U0-C") (pin "32") (pinfunction "VREF+_32") (pintype "input"))
      (node (ref "U0-C") (pin "33") (pinfunction "VDDA_33") (pintype "power_in"))
    )
    (net (code "149") (name "VUSB") (class "Default")
      (node (ref "C1-1P") (pin "1") (pinfunction "1_1") (pintype "passive"))
      (node (ref "D1-1P") (pin "A") (pinfunction "A_A") (pintype "passive"))
      (node (ref "J2-C") (pin "1") (pinfunction "VBUS_1") (pintype "power_in"))
      (node (ref "JP-CP") (pin "4") (pinfunction "4_4") (pintype "passive"))
      (node (ref "U1-P") (pin "4") (pinfunction "VDD_4") (pintype "power_in"))
    )
    (net (code "150") (name "V_LDO_IN") (class "Default")
      (node (ref "C1-11P") (pin "1") (pinfunction "1_1") (pintype "passive"))
      (node (ref "C1-2P") (pin "1") (pinfunction "1_1") (pintype "passive"))
      (node (ref "C2-2P") (pin "1") (pinfunction "1_1") (pintype "passive"))
      (node (ref "D1-11P") (pin "1") (pinfunction "K_1") (pintype "bidirectional"))
      (node (ref "R1-11P") (pin "2") (pinfunction "2_2") (pintype "passive"))
      (node (ref "U2-P") (pin "10") (pinfunction "VIN_10") (pintype "bidirectional"))
      (node (ref "U2-P") (pin "11") (pinfunction "EN_11") (pintype "bidirectional"))
      (node (ref "U2-P") (pin "6") (pinfunction "PVIN_1_6") (pintype "bidirectional"))
      (node (ref "U2-P") (pin "7") (pinfunction "PVIN_2_7") (pintype "bidirectional"))
      (node (ref "U2-P") (pin "8") (pinfunction "PVIN_3_8") (pintype "bidirectional"))
      (node (ref "U2-P") (pin "9") (pinfunction "PVIN_4_9") (pintype "bidirectional"))
    )
    (net (code "151") (name "WP") (class "Default")
      (node (ref "U0-C") (pin "78") (pinfunction "PD9_78") (pintype "bidirectional"))
      (node (ref "U1-C") (pin "3") (pinfunction "~{WP}/IO2_3") (pintype "bidirectional"))
    )
    (net (code "152") (name "unconnected-(J1-9P-Pad1)") (class "Default")
      (node (ref "J1-9P") (pin "1") (pinfunction "1_1") (pintype "passive"))
    )
    (net (code "153") (name "unconnected-(J1-9P-Pad2)") (class "Default")
      (node (ref "J1-9P") (pin "2") (pinfunction "2_2") (pintype "passive"))
    )
    (net (code "154") (name "unconnected-(J1-9P-Pad3)") (class "Default")
      (node (ref "J1-9P") (pin "3") (pinfunction "3_3") (pintype "passive"))
    )
    (net (code "155") (name "unconnected-(J1-9P-Pad4)") (class "Default")
      (node (ref "J1-9P") (pin "4") (pinfunction "4_4") (pintype "passive"))
    )
    (net (code "156") (name "unconnected-(J1-9P-Pad6)") (class "Default")
      (node (ref "J1-9P") (pin "6") (pinfunction "6_6") (pintype "passive"))
    )
    (net (code "157") (name "unconnected-(J1-9P-Pad8)") (class "Default")
      (node (ref "J1-9P") (pin "8") (pinfunction "8_8") (pintype "passive"))
    )
    (net (code "158") (name "unconnected-(J1-9P-Pad10)") (class "Default")
      (node (ref "J1-9P") (pin "10") (pinfunction "10_10") (pintype "passive"))
    )
    (net (code "159") (name "unconnected-(J1-9P-Pad11)") (class "Default")
      (node (ref "J1-9P") (pin "11") (pinfunction "11_11") (pintype "passive"))
    )
    (net (code "160") (name "unconnected-(J1-9P-Pad12)") (class "Default")
      (node (ref "J1-9P") (pin "12") (pinfunction "12_12") (pintype "passive"))
    )
    (net (code "161") (name "unconnected-(J1-9P-Pad16)") (class "Default")
      (node (ref "J1-9P") (pin "16") (pinfunction "16_16") (pintype "passive"))
    )
    (net (code "162") (name "unconnected-(JP-CS-Pad4)") (class "Default")
      (node (ref "JP-CS") (pin "4") (pinfunction "4_4") (pintype "passive"))
    )
    (net (code "163") (name "unconnected-(S0-0C-P1-Pad4)") (class "Default")
      (node (ref "S0-0C") (pin "4") (pinfunction "P1_4") (pintype "passive"))
    )
    (net (code "164") (name "unconnected-(S0-0C-S1-Pad2)") (class "Default")
      (node (ref "S0-0C") (pin "2") (pinfunction "S1_2") (pintype "passive"))
    )
    (net (code "165") (name "unconnected-(S1-P-PadO)") (class "Default")
      (node (ref "S1-P") (pin "O") (pinfunction "O_O") (pintype "passive"))
    )
    (net (code "166") (name "unconnected-(U0-C-PA4-Pad40)") (class "Default")
      (node (ref "U0-C") (pin "40") (pinfunction "PA4_40") (pintype "bidirectional"))
    )
    (net (code "167") (name "unconnected-(U0-C-PA9-Pad101)") (class "Default")
      (node (ref "U0-C") (pin "101") (pinfunction "PA9_101") (pintype "bidirectional"))
    )
    (net (code "168") (name "unconnected-(U0-C-PA15-Pad110)") (class "Default")
      (node (ref "U0-C") (pin "110") (pinfunction "PA15_110") (pintype "bidirectional"))
    )
    (net (code "169") (name "unconnected-(U0-C-PB2-Pad48)") (class "Default")
      (node (ref "U0-C") (pin "48") (pinfunction "PB2_48") (pintype "bidirectional"))
    )
    (net (code "170") (name "unconnected-(U0-C-PB4-Pad134)") (class "Default")
      (node (ref "U0-C") (pin "134") (pinfunction "PB4_134") (pintype "bidirectional"))
    )
    (net (code "171") (name "unconnected-(U0-C-PB5-Pad135)") (class "Default")
      (node (ref "U0-C") (pin "135") (pinfunction "PB5_135") (pintype "bidirectional"))
    )
    (net (code "172") (name "unconnected-(U0-C-PB6-Pad136)") (class "Default")
      (node (ref "U0-C") (pin "136") (pinfunction "PB6_136") (pintype "bidirectional"))
    )
    (net (code "173") (name "unconnected-(U0-C-PB7-Pad137)") (class "Default")
      (node (ref "U0-C") (pin "137") (pinfunction "PB7_137") (pintype "bidirectional"))
    )
    (net (code "174") (name "unconnected-(U0-C-PB8-Pad139)") (class "Default")
      (node (ref "U0-C") (pin "139") (pinfunction "PB8_139") (pintype "bidirectional"))
    )
    (net (code "175") (name "unconnected-(U0-C-PB9-Pad140)") (class "Default")
      (node (ref "U0-C") (pin "140") (pinfunction "PB9_140") (pintype "bidirectional"))
    )
    (net (code "176") (name "unconnected-(U0-C-PB12-Pad73)") (class "Default")
      (node (ref "U0-C") (pin "73") (pinfunction "PB12_73") (pintype "bidirectional"))
    )
    (net (code "177") (name "unconnected-(U0-C-PB13-Pad74)") (class "Default")
      (node (ref "U0-C") (pin "74") (pinfunction "PB13_74") (pintype "bidirectional"))
    )
    (net (code "178") (name "unconnected-(U0-C-PB14-Pad75)") (class "Default")
      (node (ref "U0-C") (pin "75") (pinfunction "PB14_75") (pintype "bidirectional"))
    )
    (net (code "179") (name "unconnected-(U0-C-PB15-Pad76)") (class "Default")
      (node (ref "U0-C") (pin "76") (pinfunction "PB15_76") (pintype "bidirectional"))
    )
    (net (code "180") (name "unconnected-(U0-C-PC0-Pad26)") (class "Default")
      (node (ref "U0-C") (pin "26") (pinfunction "PC0_26") (pintype "bidirectional"))
    )
    (net (code "181") (name "unconnected-(U0-C-PC1-Pad27)") (class "Default")
      (node (ref "U0-C") (pin "27") (pinfunction "PC1_27") (pintype "bidirectional"))
    )
    (net (code "182") (name "unconnected-(U0-C-PC2-Pad28)") (class "Default")
      (node (ref "U0-C") (pin "28") (pinfunction "PC2_28") (pintype "bidirectional"))
    )
    (net (code "183") (name "unconnected-(U0-C-PC3-Pad29)") (class "Default")
      (node (ref "U0-C") (pin "29") (pinfunction "PC3_29") (pintype "bidirectional"))
    )
    (net (code "184") (name "unconnected-(U0-C-PC13-Pad7)") (class "Default")
      (node (ref "U0-C") (pin "7") (pinfunction "PC13_7") (pintype "bidirectional"))
    )
    (net (code "185") (name "unconnected-(U0-C-PC14-Pad8)") (class "Default")
      (node (ref "U0-C") (pin "8") (pinfunction "PC14_8") (pintype "bidirectional"))
    )
    (net (code "186") (name "unconnected-(U0-C-PC15-Pad9)") (class "Default")
      (node (ref "U0-C") (pin "9") (pinfunction "PC15_9") (pintype "bidirectional"))
    )
    (net (code "187") (name "unconnected-(U0-C-PD1-Pad115)") (class "Default")
      (node (ref "U0-C") (pin "115") (pinfunction "PD1_115") (pintype "bidirectional"))
    )
    (net (code "188") (name "unconnected-(U0-C-PD2-Pad116)") (class "Default")
      (node (ref "U0-C") (pin "116") (pinfunction "PD2_116") (pintype "bidirectional"))
    )
    (net (code "189") (name "unconnected-(U0-C-PD3-Pad117)") (class "Default")
      (node (ref "U0-C") (pin "117") (pinfunction "PD3_117") (pintype "bidirectional"))
    )
    (net (code "190") (name "unconnected-(U0-C-PD4-Pad118)") (class "Default")
      (node (ref "U0-C") (pin "118") (pinfunction "PD4_118") (pintype "bidirectional"))
    )
    (net (code "191") (name "unconnected-(U0-C-PD5-Pad119)") (class "Default")
      (node (ref "U0-C") (pin "119") (pinfunction "PD5_119") (pintype "bidirectional"))
    )
    (net (code "192") (name "unconnected-(U0-C-PD6-Pad122)") (class "Default")
      (node (ref "U0-C") (pin "122") (pinfunction "PD6_122") (pintype "bidirectional"))
    )
    (net (code "193") (name "unconnected-(U0-C-PD7-Pad123)") (class "Default")
      (node (ref "U0-C") (pin "123") (pinfunction "PD7_123") (pintype "bidirectional"))
    )
    (net (code "194") (name "unconnected-(U0-C-PD10-Pad79)") (class "Default")
      (node (ref "U0-C") (pin "79") (pinfunction "PD10_79") (pintype "bidirectional"))
    )
    (net (code "195") (name "unconnected-(U0-C-PD11-Pad80)") (class "Default")
      (node (ref "U0-C") (pin "80") (pinfunction "PD11_80") (pintype "bidirectional"))
    )
    (net (code "196") (name "unconnected-(U0-C-PD12-Pad81)") (class "Default")
      (node (ref "U0-C") (pin "81") (pinfunction "PD12_81") (pintype "bidirectional"))
    )
    (net (code "197") (name "unconnected-(U0-C-PD13-Pad82)") (class "Default")
      (node (ref "U0-C") (pin "82") (pinfunction "PD13_82") (pintype "bidirectional"))
    )
    (net (code "198") (name "unconnected-(U0-C-PD14-Pad85)") (class "Default")
      (node (ref "U0-C") (pin "85") (pinfunction "PD14_85") (pintype "bidirectional"))
    )
    (net (code "199") (name "unconnected-(U0-C-PD15-Pad86)") (class "Default")
      (node (ref "U0-C") (pin "86") (pinfunction "PD15_86") (pintype "bidirectional"))
    )
    (net (code "200") (name "unconnected-(U0-C-PE0-Pad141)") (class "Default")
      (node (ref "U0-C") (pin "141") (pinfunction "PE0_141") (pintype "bidirectional"))
    )
    (net (code "201") (name "unconnected-(U0-C-PE1-Pad142)") (class "Default")
      (node (ref "U0-C") (pin "142") (pinfunction "PE1_142") (pintype "bidirectional"))
    )
    (net (code "202") (name "unconnected-(U0-C-PE3-Pad2)") (class "Default")
      (node (ref "U0-C") (pin "2") (pinfunction "PE3_2") (pintype "bidirectional"))
    )
    (net (code "203") (name "unconnected-(U0-C-PE4-Pad3)") (class "Default")
      (node (ref "U0-C") (pin "3") (pinfunction "PE4_3") (pintype "bidirectional"))
    )
    (net (code "204") (name "unconnected-(U0-C-PE5-Pad4)") (class "Default")
      (node (ref "U0-C") (pin "4") (pinfunction "PE5_4") (pintype "bidirectional"))
    )
    (net (code "205") (name "unconnected-(U0-C-PE6-Pad5)") (class "Default")
      (node (ref "U0-C") (pin "5") (pinfunction "PE6_5") (pintype "bidirectional"))
    )
    (net (code "206") (name "unconnected-(U0-C-PE9-Pad60)") (class "Default")
      (node (ref "U0-C") (pin "60") (pinfunction "PE9_60") (pintype "bidirectional"))
    )
    (net (code "207") (name "unconnected-(U0-C-PF0-Pad10)") (class "Default")
      (node (ref "U0-C") (pin "10") (pinfunction "PF0_10") (pintype "bidirectional"))
    )
    (net (code "208") (name "unconnected-(U0-C-PF5-Pad15)") (class "Default")
      (node (ref "U0-C") (pin "15") (pinfunction "PF5_15") (pintype "bidirectional"))
    )
    (net (code "209") (name "unconnected-(U0-C-PF10-Pad22)") (class "Default")
      (node (ref "U0-C") (pin "22") (pinfunction "PF10_22") (pintype "bidirectional"))
    )
    (net (code "210") (name "unconnected-(U0-C-PF11-Pad49)") (class "Default")
      (node (ref "U0-C") (pin "49") (pinfunction "PF11_49") (pintype "bidirectional"))
    )
    (net (code "211") (name "unconnected-(U0-C-PF12-Pad50)") (class "Default")
      (node (ref "U0-C") (pin "50") (pinfunction "PF12_50") (pintype "bidirectional"))
    )
    (net (code "212") (name "unconnected-(U0-C-PG2-Pad87)") (class "Default")
      (node (ref "U0-C") (pin "87") (pinfunction "PG2_87") (pintype "bidirectional"))
    )
    (net (code "213") (name "unconnected-(U0-C-PG3-Pad88)") (class "Default")
      (node (ref "U0-C") (pin "88") (pinfunction "PG3_88") (pintype "bidirectional"))
    )
    (net (code "214") (name "unconnected-(U0-C-PG5-Pad90)") (class "Default")
      (node (ref "U0-C") (pin "90") (pinfunction "PG5_90") (pintype "bidirectional"))
    )
    (net (code "215") (name "unconnected-(U0-C-PG6-Pad91)") (class "Default")
      (node (ref "U0-C") (pin "91") (pinfunction "PG6_91") (pintype "bidirectional"))
    )
    (net (code "216") (name "unconnected-(U0-C-PG7-Pad92)") (class "Default")
      (node (ref "U0-C") (pin "92") (pinfunction "PG7_92") (pintype "bidirectional"))
    )
    (net (code "217") (name "unconnected-(U0-C-PG8-Pad93)") (class "Default")
      (node (ref "U0-C") (pin "93") (pinfunction "PG8_93") (pintype "bidirectional"))
    )
    (net (code "218") (name "unconnected-(U0-C-PG9-Pad124)") (class "Default")
      (node (ref "U0-C") (pin "124") (pinfunction "PG9_124") (pintype "bidirectional"))
    )
    (net (code "219") (name "unconnected-(U0-C-PG10-Pad125)") (class "Default")
      (node (ref "U0-C") (pin "125") (pinfunction "PG10_125") (pintype "bidirectional"))
    )
    (net (code "220") (name "unconnected-(U0-C-PG11-Pad126)") (class "Default")
      (node (ref "U0-C") (pin "126") (pinfunction "PG11_126") (pintype "bidirectional"))
    )
    (net (code "221") (name "unconnected-(U0-C-PG12-Pad127)") (class "Default")
      (node (ref "U0-C") (pin "127") (pinfunction "PG12_127") (pintype "bidirectional"))
    )
    (net (code "222") (name "unconnected-(U0-C-PG13-Pad128)") (class "Default")
      (node (ref "U0-C") (pin "128") (pinfunction "PG13_128") (pintype "bidirectional"))
    )
    (net (code "223") (name "unconnected-(U0-C-PG14-Pad129)") (class "Default")
      (node (ref "U0-C") (pin "129") (pinfunction "PG14_129") (pintype "bidirectional"))
    )
    (net (code "224") (name "unconnected-(U0-C-PG15-Pad132)") (class "Default")
      (node (ref "U0-C") (pin "132") (pinfunction "PG15_132") (pintype "bidirectional"))
    )
    (net (code "225") (name "unconnected-(U1-C-EP-Pad9)") (class "Default")
      (node (ref "U1-C") (pin "9") (pinfunction "EP_9") (pintype "bidirectional"))
    )
    (net (code "226") (name "unconnected-(U1-S-AUX_CL-Pad7)") (class "Default")
      (node (ref "U1-S") (pin "7") (pinfunction "AUX_CL_7") (pintype "bidirectional"))
    )
    (net (code "227") (name "unconnected-(U1-S-AUX_DA-Pad21)") (class "Default")
      (node (ref "U1-S") (pin "21") (pinfunction "AUX_DA_21") (pintype "bidirectional"))
    )
    (net (code "228") (name "unconnected-(U1-S-FSYNC-Pad11)") (class "Default")
      (node (ref "U1-S") (pin "11") (pinfunction "FSYNC_11") (pintype "bidirectional"))
    )
    (net (code "229") (name "unconnected-(U1-S-INT1-Pad12)") (class "Default")
      (node (ref "U1-S") (pin "12") (pinfunction "INT1_12") (pintype "bidirectional"))
    )
    (net (code "230") (name "unconnected-(U1-S-NC.1-Pad1)") (class "Default")
      (node (ref "U1-S") (pin "1") (pinfunction "NC.1_1") (pintype "bidirectional"))
    )
    (net (code "231") (name "unconnected-(U1-S-NC.2-Pad2)") (class "Default")
      (node (ref "U1-S") (pin "2") (pinfunction "NC.2_2") (pintype "bidirectional"))
    )
    (net (code "232") (name "unconnected-(U1-S-NC.3-Pad3)") (class "Default")
      (node (ref "U1-S") (pin "3") (pinfunction "NC.3_3") (pintype "bidirectional"))
    )
    (net (code "233") (name "unconnected-(U1-S-NC.4-Pad4)") (class "Default")
      (node (ref "U1-S") (pin "4") (pinfunction "NC.4_4") (pintype "bidirectional"))
    )
    (net (code "234") (name "unconnected-(U1-S-NC.5-Pad5)") (class "Default")
      (node (ref "U1-S") (pin "5") (pinfunction "NC.5_5") (pintype "bidirectional"))
    )
    (net (code "235") (name "unconnected-(U1-S-NC.6-Pad6)") (class "Default")
      (node (ref "U1-S") (pin "6") (pinfunction "NC.6_6") (pintype "bidirectional"))
    )
    (net (code "236") (name "unconnected-(U1-S-NC.14-Pad14)") (class "Default")
      (node (ref "U1-S") (pin "14") (pinfunction "NC.14_14") (pintype "bidirectional"))
    )
    (net (code "237") (name "unconnected-(U1-S-NC.15-Pad15)") (class "Default")
      (node (ref "U1-S") (pin "15") (pinfunction "NC.15_15") (pintype "bidirectional"))
    )
    (net (code "238") (name "unconnected-(U1-S-NC.16-Pad16)") (class "Default")
      (node (ref "U1-S") (pin "16") (pinfunction "NC.16_16") (pintype "bidirectional"))
    )
    (net (code "239") (name "unconnected-(U1-S-NC.17-Pad17)") (class "Default")
      (node (ref "U1-S") (pin "17") (pinfunction "NC.17_17") (pintype "bidirectional"))
    )
    (net (code "240") (name "unconnected-(U1-S-RESV.NC-Pad19)") (class "Default")
      (node (ref "U1-S") (pin "19") (pinfunction "RESV.NC_19") (pintype "bidirectional"))
    )
    (net (code "241") (name "unconnected-(U2-P-EP-Pad21)") (class "Default")
      (node (ref "U2-P") (pin "21") (pinfunction "EP_21") (pintype "bidirectional"))
    )
    (net (code "242") (name "unconnected-(U2-P-LX1_2-Pad5)") (class "Default")
      (node (ref "U2-P") (pin "5") (pinfunction "LX1_2_5") (pintype "bidirectional"))
    )
    (net (code "243") (name "unconnected-(U2-P-LX2_2-Pad2)") (class "Default")
      (node (ref "U2-P") (pin "2") (pinfunction "LX2_2_2") (pintype "bidirectional"))
    )
    (net (code "244") (name "unconnected-(U2-P-NC-Pad16)") (class "Default")
      (node (ref "U2-P") (pin "16") (pinfunction "NC_16") (pintype "no_connect"))
    )
    (net (code "245") (name "unconnected-(U2-P-SGND_2-Pad14)") (class "Default")
      (node (ref "U2-P") (pin "14") (pinfunction "SGND_2_14") (pintype "bidirectional"))
    )
    (net (code "246") (name "unconnected-(U4-S-1PPS-Pad13)") (class "Default")
      (node (ref "U4-S") (pin "13") (pinfunction "1PPS_13") (pintype "bidirectional"))
    )
    (net (code "247") (name "unconnected-(U4-S-NREST-Pad2)") (class "Default")
      (node (ref "U4-S") (pin "2") (pinfunction "NREST_2") (pintype "bidirectional"))
    )
    (net (code "248") (name "unconnected-(U4-S-RTCM-Pad14)") (class "Default")
      (node (ref "U4-S") (pin "14") (pinfunction "RTCM_14") (pintype "bidirectional"))
    )
    (net (code "249") (name "unconnected-(U4-S-VBACKUP-Pad4)") (class "Default")
      (node (ref "U4-S") (pin "4") (pinfunction "VBACKUP_4") (pintype "bidirectional"))
    )
  )
)
